# baseboard_rev_0_2.net
KiCad netlist of a schematic drawn in EAGLE
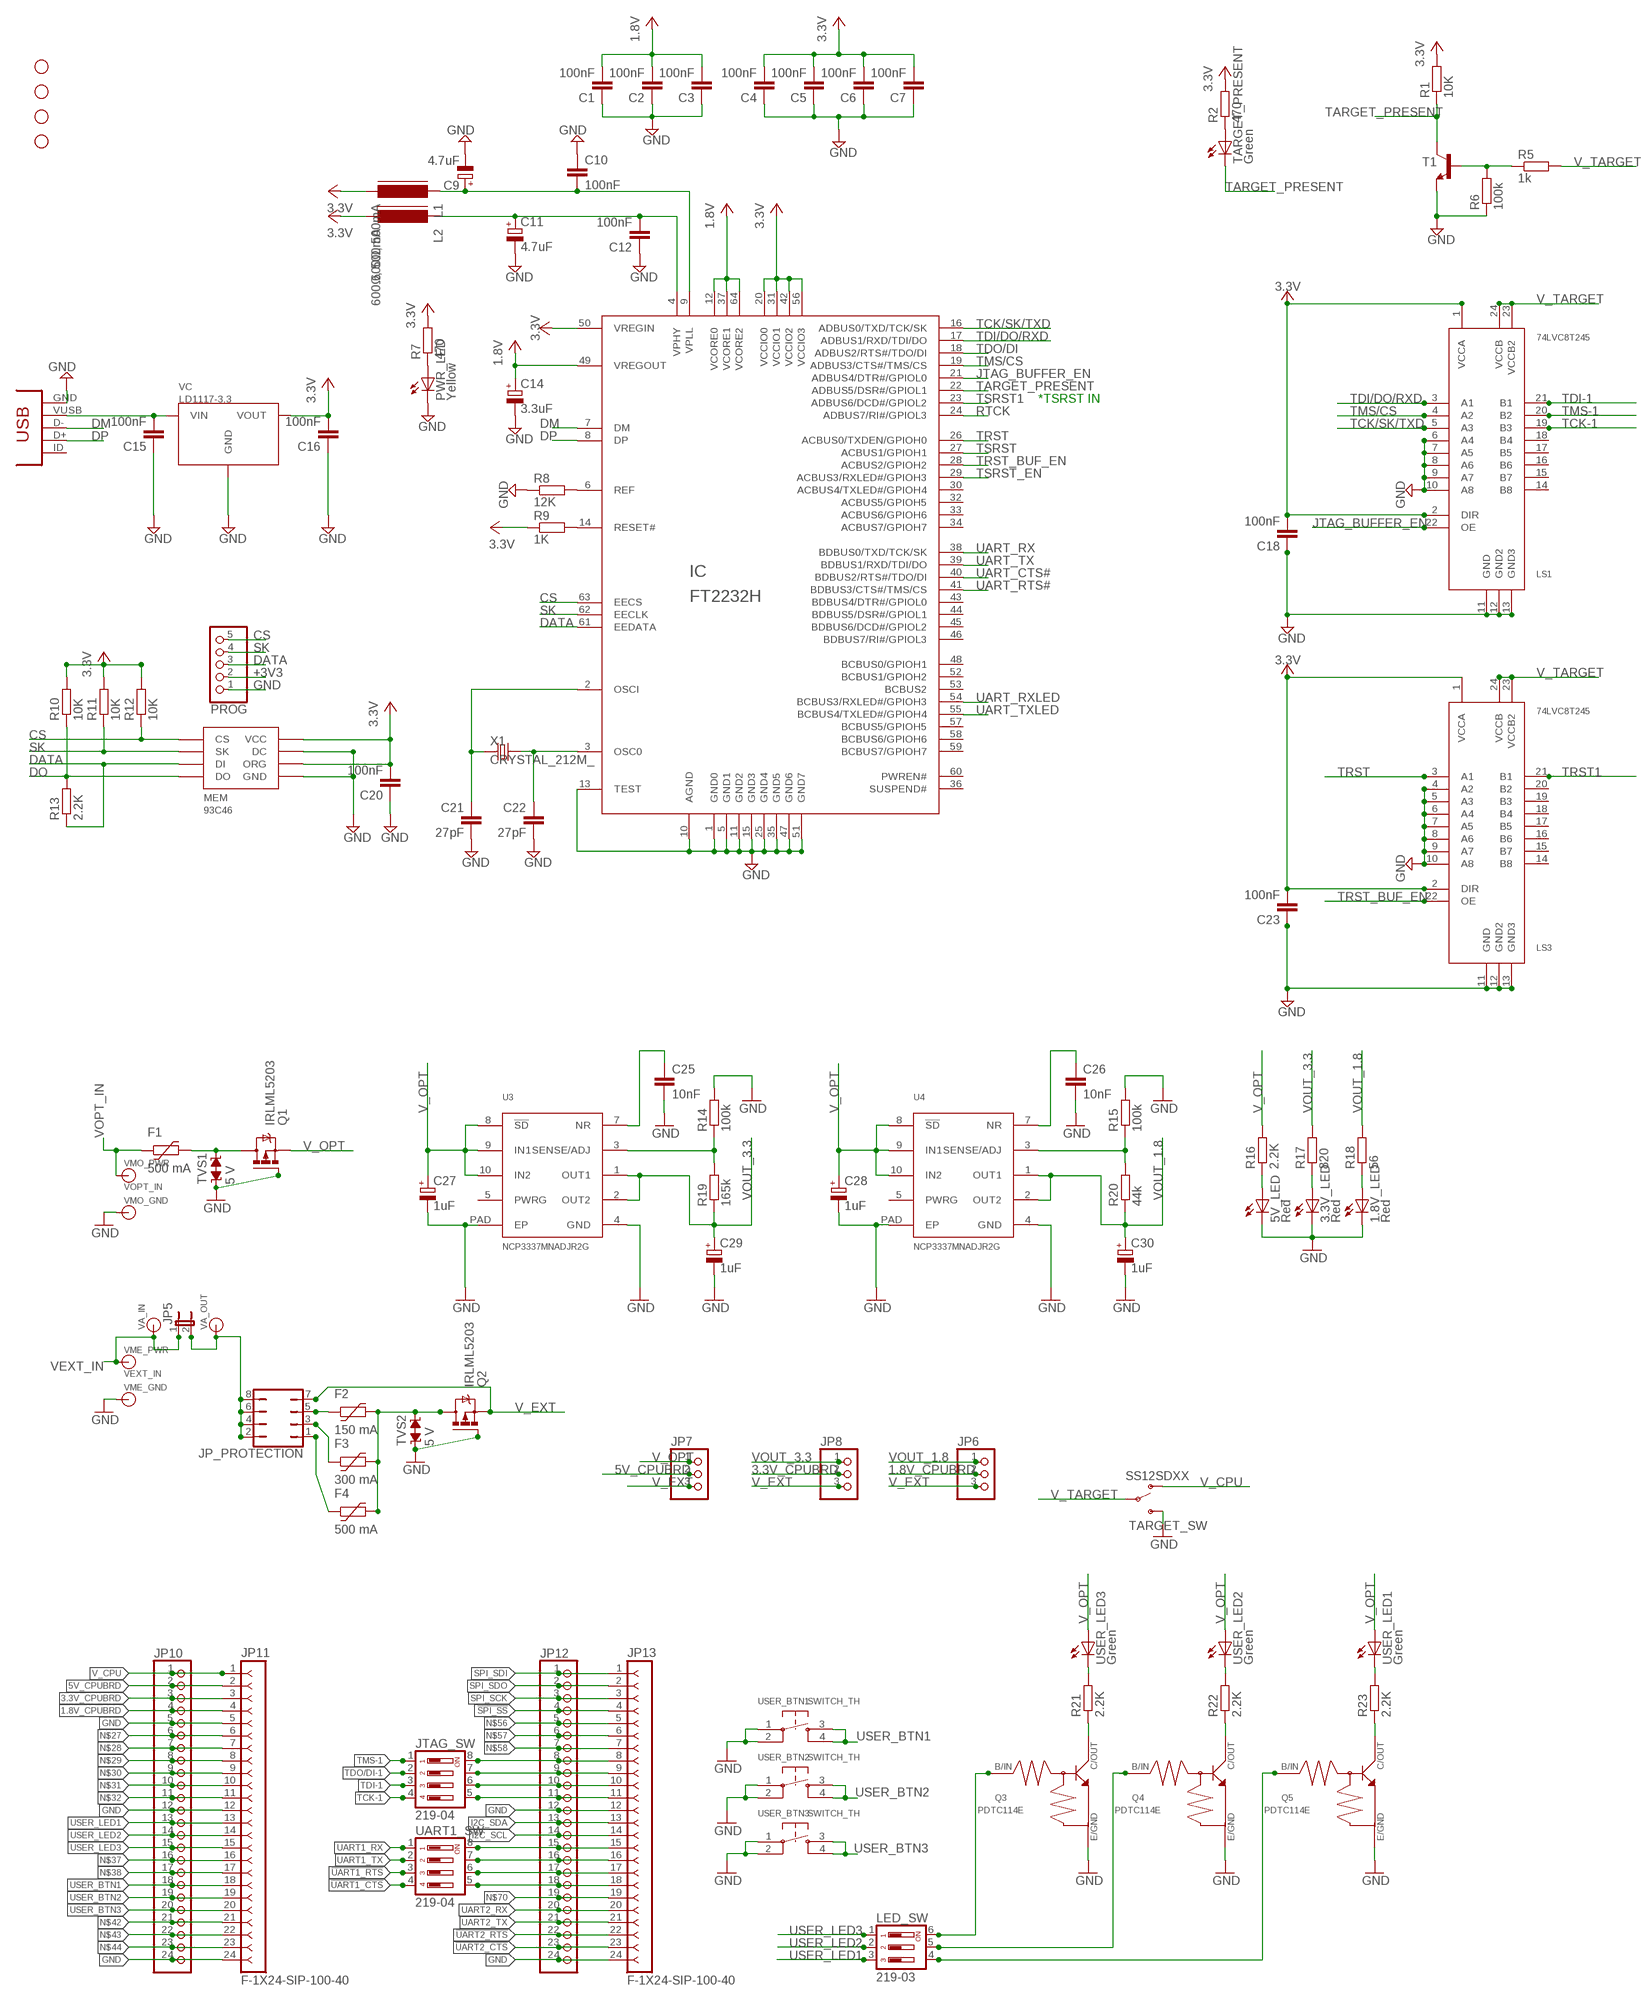
[diagram p0: schematic, sheet 1, part 1 of 2]
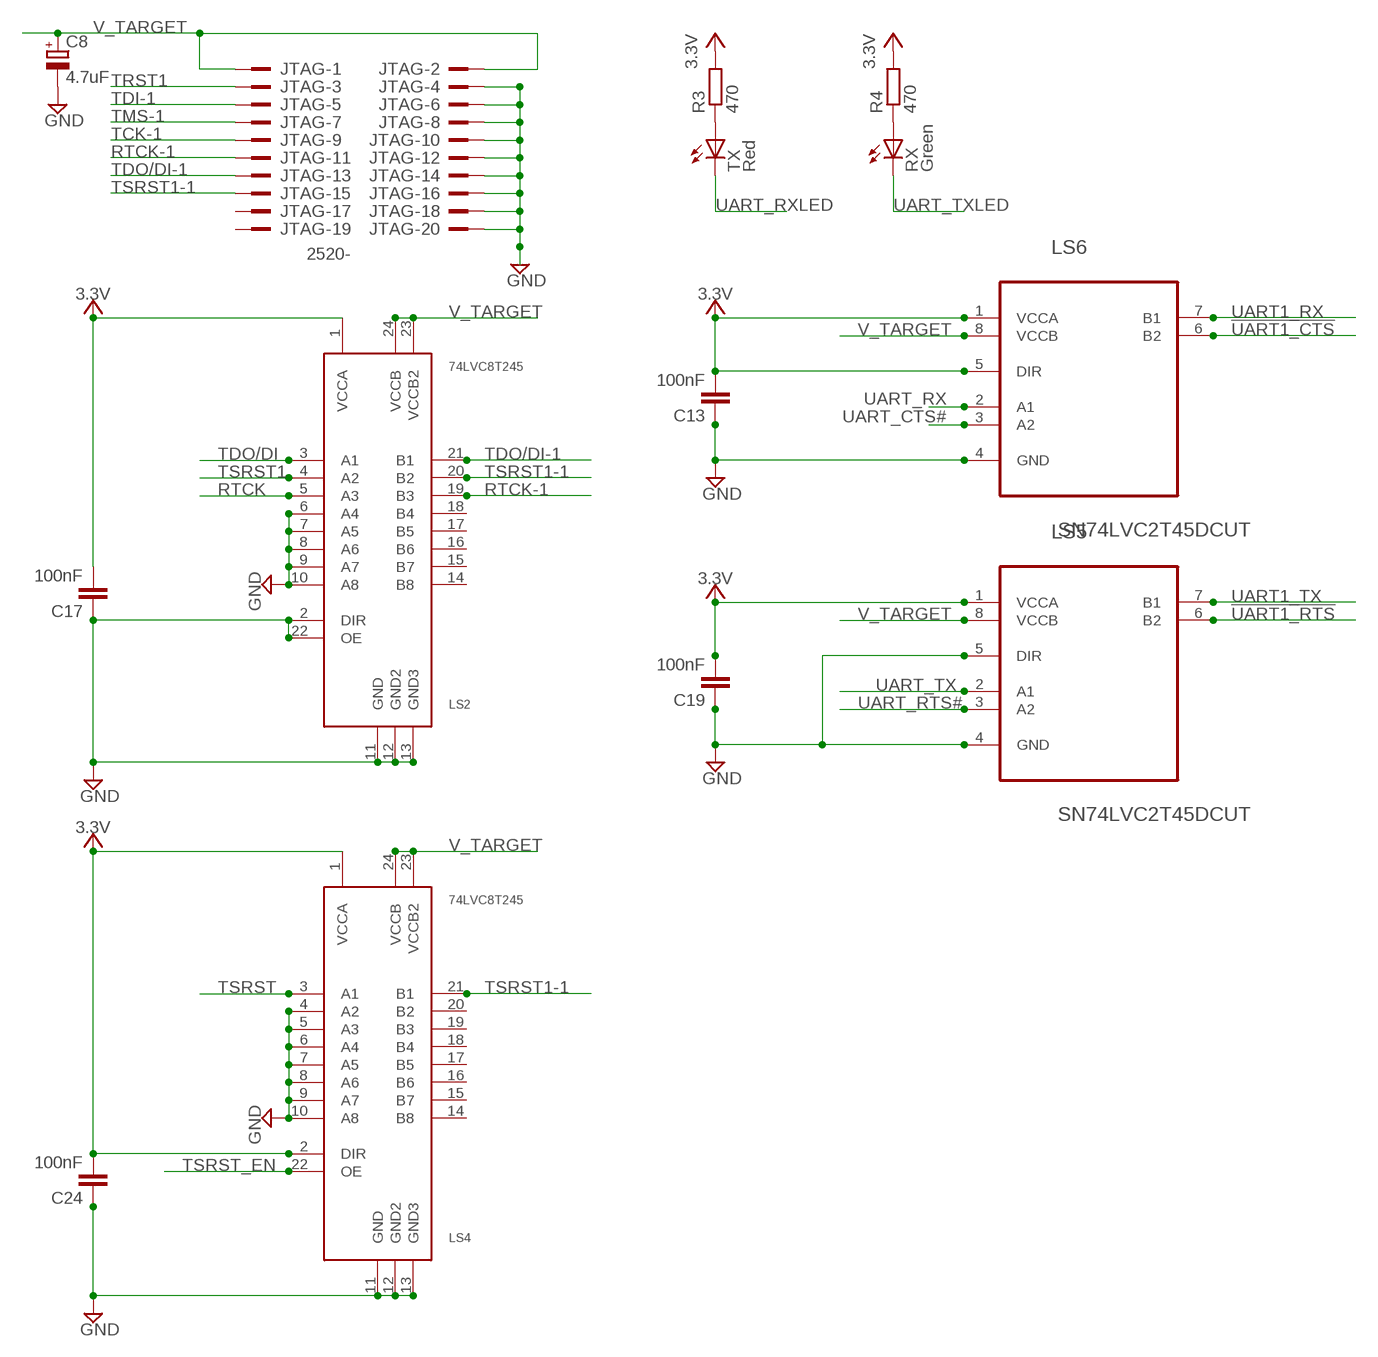
[diagram p1: schematic, sheet 1, part 2 of 2]

(export (version "E")
  (design (tool "Eeschema 10.0.6"))
  (components
    (comp (ref "1.8V_LED")
      (value "Red")
      (footprint "eagle-import:CHIPLED_0805")
      (libsource (lib "eagle-import") (part "LEDCHIPLED_0805"))
    )
    (comp (ref "3.3V_LED")
      (value "Red")
      (footprint "eagle-import:CHIPLED_0805")
      (libsource (lib "eagle-import") (part "LEDCHIPLED_0805"))
    )
    (comp (ref "5V_LED")
      (value "Red")
      (footprint "eagle-import:CHIPLED_0805")
      (libsource (lib "eagle-import") (part "LEDCHIPLED_0805"))
    )
    (comp (ref "C1")
      (value "100nF")
      (footprint "eagle-import:C805")
      (libsource (lib "eagle-import") (part "CAPC805"))
    )
    (comp (ref "C2")
      (value "100nF")
      (footprint "eagle-import:C805")
      (libsource (lib "eagle-import") (part "CAPC805"))
    )
    (comp (ref "C3")
      (value "100nF")
      (footprint "eagle-import:C805")
      (libsource (lib "eagle-import") (part "CAPC805"))
    )
    (comp (ref "C4")
      (value "100nF")
      (footprint "eagle-import:C805")
      (libsource (lib "eagle-import") (part "CAPC805"))
    )
    (comp (ref "C5")
      (value "100nF")
      (footprint "eagle-import:C805")
      (libsource (lib "eagle-import") (part "CAPC805"))
    )
    (comp (ref "C6")
      (value "100nF")
      (footprint "eagle-import:C805")
      (libsource (lib "eagle-import") (part "CAPC805"))
    )
    (comp (ref "C7")
      (value "100nF")
      (footprint "eagle-import:C805")
      (libsource (lib "eagle-import") (part "CAPC805"))
    )
    (comp (ref "C8")
      (value "4.7uF")
      (footprint "eagle-import:SMC_A")
      (libsource (lib "eagle-import") (part "CAP_POLSMC_A"))
    )
    (comp (ref "C9")
      (value "4.7uF")
      (footprint "eagle-import:SMC_A")
      (libsource (lib "eagle-import") (part "CAP_POLSMC_A"))
    )
    (comp (ref "C10")
      (value "100nF")
      (footprint "eagle-import:C805")
      (libsource (lib "eagle-import") (part "CAPC805"))
    )
    (comp (ref "C11")
      (value "4.7uF")
      (footprint "eagle-import:SMC_A")
      (libsource (lib "eagle-import") (part "CAP_POLSMC_A"))
    )
    (comp (ref "C12")
      (value "100nF")
      (footprint "eagle-import:C805")
      (libsource (lib "eagle-import") (part "CAPC805"))
    )
    (comp (ref "C13")
      (value "100nF")
      (footprint "eagle-import:C805")
      (libsource (lib "eagle-import") (part "CAPC805"))
    )
    (comp (ref "C14")
      (value "3.3uF")
      (footprint "eagle-import:SMC_A")
      (libsource (lib "eagle-import") (part "CAP_POLSMC_A"))
    )
    (comp (ref "C15")
      (value "100nF")
      (footprint "eagle-import:C805")
      (libsource (lib "eagle-import") (part "CAPC805"))
    )
    (comp (ref "C16")
      (value "100nF")
      (footprint "eagle-import:C805")
      (libsource (lib "eagle-import") (part "CAPC805"))
    )
    (comp (ref "C17")
      (value "100nF")
      (footprint "eagle-import:C805")
      (libsource (lib "eagle-import") (part "CAPC805"))
    )
    (comp (ref "C18")
      (value "100nF")
      (footprint "eagle-import:C805")
      (libsource (lib "eagle-import") (part "CAPC805"))
    )
    (comp (ref "C19")
      (value "100nF")
      (footprint "eagle-import:C805")
      (libsource (lib "eagle-import") (part "CAPC805"))
    )
    (comp (ref "C20")
      (value "100nF")
      (footprint "eagle-import:C805")
      (libsource (lib "eagle-import") (part "CAPC805"))
    )
    (comp (ref "C21")
      (value "27pF")
      (footprint "eagle-import:C805")
      (libsource (lib "eagle-import") (part "CAPC805"))
    )
    (comp (ref "C22")
      (value "27pF")
      (footprint "eagle-import:C805")
      (libsource (lib "eagle-import") (part "CAPC805"))
    )
    (comp (ref "C23")
      (value "100nF")
      (footprint "eagle-import:C805")
      (libsource (lib "eagle-import") (part "CAPC805"))
    )
    (comp (ref "C24")
      (value "100nF")
      (footprint "eagle-import:C805")
      (libsource (lib "eagle-import") (part "CAPC805"))
    )
    (comp (ref "C25")
      (value "10nF")
      (footprint "eagle-import:C0805")
      (libsource (lib "eagle-import") (part "C-EUC0805"))
    )
    (comp (ref "C26")
      (value "10nF")
      (footprint "eagle-import:C0805")
      (libsource (lib "eagle-import") (part "C-EUC0805"))
    )
    (comp (ref "C27")
      (value "1uF")
      (footprint "eagle-import:PANASONIC_B")
      (libsource (lib "eagle-import") (part "CPOL-EUB"))
    )
    (comp (ref "C28")
      (value "1uF")
      (footprint "eagle-import:PANASONIC_B")
      (libsource (lib "eagle-import") (part "CPOL-EUB"))
    )
    (comp (ref "C29")
      (value "1uF")
      (footprint "eagle-import:PANASONIC_B")
      (libsource (lib "eagle-import") (part "CPOL-EUB"))
    )
    (comp (ref "C30")
      (value "1uF")
      (footprint "eagle-import:PANASONIC_B")
      (libsource (lib "eagle-import") (part "CPOL-EUB"))
    )
    (comp (ref "CONN1")
      (value "CONN_USB")
      (footprint "eagle-import:CONN_USB_MINI-B")
      (libsource (lib "eagle-import") (part "CONN_USB"))
    )
    (comp (ref "F1")
      (value "500 mA")
      (footprint "eagle-import:1206L")
      (libsource (lib "eagle-import") (part "1206L"))
    )
    (comp (ref "F2")
      (value "150 mA")
      (footprint "eagle-import:1206L")
      (libsource (lib "eagle-import") (part "1206L"))
    )
    (comp (ref "F3")
      (value "300 mA")
      (footprint "eagle-import:1206L")
      (libsource (lib "eagle-import") (part "1206L"))
    )
    (comp (ref "F4")
      (value "500 mA")
      (footprint "eagle-import:1206L")
      (libsource (lib "eagle-import") (part "1206L"))
    )
    (comp (ref "IC")
      (value "FT2232H")
      (footprint "eagle-import:LQFP64")
      (libsource (lib "eagle-import") (part "FT2232H"))
    )
    (comp (ref "JP1")
      (value "STAND-OFF")
      (footprint "eagle-import:STAND-OFF")
      (libsource (lib "eagle-import") (part "STAND-OFF"))
    )
    (comp (ref "JP2")
      (value "STAND-OFF")
      (footprint "eagle-import:STAND-OFF")
      (libsource (lib "eagle-import") (part "STAND-OFF"))
    )
    (comp (ref "JP3")
      (value "STAND-OFF")
      (footprint "eagle-import:STAND-OFF")
      (libsource (lib "eagle-import") (part "STAND-OFF"))
    )
    (comp (ref "JP4")
      (value "STAND-OFF")
      (footprint "eagle-import:STAND-OFF")
      (libsource (lib "eagle-import") (part "STAND-OFF"))
    )
    (comp (ref "JP5")
      (value "JUMPER-2PTH")
      (footprint "eagle-import:1X02")
      (libsource (lib "eagle-import") (part "JUMPER-2PTH"))
    )
    (comp (ref "JP6")
      (value "PINHD-1X3")
      (footprint "eagle-import:1X03")
      (libsource (lib "eagle-import") (part "PINHD-1X3"))
    )
    (comp (ref "JP7")
      (value "PINHD-1X3")
      (footprint "eagle-import:1X03")
      (libsource (lib "eagle-import") (part "PINHD-1X3"))
    )
    (comp (ref "JP8")
      (value "PINHD-1X3")
      (footprint "eagle-import:1X03")
      (libsource (lib "eagle-import") (part "PINHD-1X3"))
    )
    (comp (ref "JP10")
      (value "PINHD-1X24")
      (footprint "eagle-import:1X24")
      (libsource (lib "eagle-import") (part "PINHD-1X24"))
    )
    (comp (ref "JP11")
      (value "F-1X24-SIP-100-40")
      (footprint "eagle-import:SIP-100-24-40")
      (libsource (lib "eagle-import") (part "F-1X24-SIP-100-40"))
    )
    (comp (ref "JP12")
      (value "PINHD-1X24")
      (footprint "eagle-import:1X24")
      (libsource (lib "eagle-import") (part "PINHD-1X24"))
    )
    (comp (ref "JP13")
      (value "F-1X24-SIP-100-40")
      (footprint "eagle-import:SIP-100-24-40")
      (libsource (lib "eagle-import") (part "F-1X24-SIP-100-40"))
    )
    (comp (ref "JP_PROTECTION")
      (value "JP4Q")
      (footprint "eagle-import:JP4Q")
      (libsource (lib "eagle-import") (part "JP4Q"))
    )
    (comp (ref "JTAG")
      (value "2520-")
      (footprint "eagle-import:PAK100_2500-20")
      (libsource (lib "eagle-import") (part "2520-"))
    )
    (comp (ref "JTAG_SW")
      (value "219-04")
      (footprint "eagle-import:CTS-219-04")
      (libsource (lib "eagle-import") (part "219-04"))
    )
    (comp (ref "L1")
      (value "600Ω, 500mA")
      (footprint "eagle-import:FB805")
      (libsource (lib "eagle-import") (part "FERRITE_BEAD805"))
    )
    (comp (ref "L2")
      (value "600Ω, 500mA")
      (footprint "eagle-import:FB805")
      (libsource (lib "eagle-import") (part "FERRITE_BEAD805"))
    )
    (comp (ref "LED_SW")
      (value "219-03")
      (footprint "eagle-import:CTS-219-03")
      (libsource (lib "eagle-import") (part "219-03"))
    )
    (comp (ref "LS1")
      (value "74LVC8T245")
      (footprint "eagle-import:TSSOP24")
      (libsource (lib "eagle-import") (part "74LVC8T245"))
    )
    (comp (ref "LS2")
      (value "74LVC8T245")
      (footprint "eagle-import:TSSOP24")
      (libsource (lib "eagle-import") (part "74LVC8T245"))
    )
    (comp (ref "LS3")
      (value "74LVC8T245")
      (footprint "eagle-import:TSSOP24")
      (libsource (lib "eagle-import") (part "74LVC8T245"))
    )
    (comp (ref "LS4")
      (value "74LVC8T245")
      (footprint "eagle-import:TSSOP24")
      (libsource (lib "eagle-import") (part "74LVC8T245"))
    )
    (comp (ref "LS5")
      (value "SN74LVC2T45DCUT")
      (footprint "eagle-import:SOP50P310X90-8N")
      (libsource (lib "eagle-import") (part "SN74LVC2T45DCUT"))
    )
    (comp (ref "LS6")
      (value "SN74LVC2T45DCUT")
      (footprint "eagle-import:SOP50P310X90-8N")
      (libsource (lib "eagle-import") (part "SN74LVC2T45DCUT"))
    )
    (comp (ref "MEM")
      (value "93C46")
      (footprint "eagle-import:SOIC8")
      (libsource (lib "eagle-import") (part "93C46"))
    )
    (comp (ref "PROG")
      (value "PINHD-1X5")
      (footprint "eagle-import:1X05")
      (libsource (lib "eagle-import") (part "PINHD-1X5"))
    )
    (comp (ref "PWR_LED")
      (value "Yellow")
      (footprint "eagle-import:CHIPLED_0805")
      (libsource (lib "eagle-import") (part "led_LEDCHIPLED_0805"))
    )
    (comp (ref "Q1")
      (value "IRLML5203")
      (footprint "eagle-import:MICRO3")
      (libsource (lib "eagle-import") (part "IRLML5203"))
    )
    (comp (ref "Q2")
      (value "IRLML5203")
      (footprint "eagle-import:MICRO3")
      (libsource (lib "eagle-import") (part "IRLML5203"))
    )
    (comp (ref "Q3")
      (value "PDTC114E")
      (footprint "eagle-import:SOT416")
      (libsource (lib "eagle-import") (part "PDTC114E"))
    )
    (comp (ref "Q4")
      (value "PDTC114E")
      (footprint "eagle-import:SOT416")
      (libsource (lib "eagle-import") (part "PDTC114E"))
    )
    (comp (ref "Q5")
      (value "PDTC114E")
      (footprint "eagle-import:SOT416")
      (libsource (lib "eagle-import") (part "PDTC114E"))
    )
    (comp (ref "R1")
      (value "10K")
      (footprint "eagle-import:R805")
      (libsource (lib "eagle-import") (part "RESISTORR805R805"))
    )
    (comp (ref "R2")
      (value "470")
      (footprint "eagle-import:R805")
      (libsource (lib "eagle-import") (part "RESISTORR805R805"))
    )
    (comp (ref "R3")
      (value "470")
      (footprint "eagle-import:R805")
      (libsource (lib "eagle-import") (part "RESISTORR805R805"))
    )
    (comp (ref "R4")
      (value "470")
      (footprint "eagle-import:R805")
      (libsource (lib "eagle-import") (part "RESISTORR805R805"))
    )
    (comp (ref "R5")
      (value "1k")
      (footprint "eagle-import:R805")
      (libsource (lib "eagle-import") (part "RESISTORR805R805"))
    )
    (comp (ref "R6")
      (value "100k")
      (footprint "eagle-import:R805")
      (libsource (lib "eagle-import") (part "RESISTORR805R805"))
    )
    (comp (ref "R7")
      (value "470")
      (footprint "eagle-import:R805")
      (libsource (lib "eagle-import") (part "RESISTORR805R805"))
    )
    (comp (ref "R8")
      (value "12K")
      (footprint "eagle-import:R805")
      (libsource (lib "eagle-import") (part "RESISTORR805R805"))
    )
    (comp (ref "R9")
      (value "1K")
      (footprint "eagle-import:R805")
      (libsource (lib "eagle-import") (part "RESISTORR805R805"))
    )
    (comp (ref "R10")
      (value "10K")
      (footprint "eagle-import:R805")
      (libsource (lib "eagle-import") (part "RESISTORR805R805"))
    )
    (comp (ref "R11")
      (value "10K")
      (footprint "eagle-import:R805")
      (libsource (lib "eagle-import") (part "RESISTORR805R805"))
    )
    (comp (ref "R12")
      (value "10K")
      (footprint "eagle-import:R805")
      (libsource (lib "eagle-import") (part "RESISTORR805R805"))
    )
    (comp (ref "R13")
      (value "2.2K")
      (footprint "eagle-import:R805")
      (libsource (lib "eagle-import") (part "RESISTORR805R805"))
    )
    (comp (ref "R14")
      (value "100k")
      (footprint "eagle-import:R0805")
      (libsource (lib "eagle-import") (part "R-EU_R0805"))
    )
    (comp (ref "R15")
      (value "100k")
      (footprint "eagle-import:R0805")
      (libsource (lib "eagle-import") (part "R-EU_R0805"))
    )
    (comp (ref "R16")
      (value "2.2K")
      (footprint "eagle-import:R0805")
      (libsource (lib "eagle-import") (part "R-EU_R0805"))
    )
    (comp (ref "R17")
      (value "820")
      (footprint "eagle-import:R0805")
      (libsource (lib "eagle-import") (part "R-EU_R0805"))
    )
    (comp (ref "R18")
      (value "56")
      (footprint "eagle-import:R0805")
      (libsource (lib "eagle-import") (part "R-EU_R0805"))
    )
    (comp (ref "R19")
      (value "165k")
      (footprint "eagle-import:R0805")
      (libsource (lib "eagle-import") (part "R-EU_R0805"))
    )
    (comp (ref "R20")
      (value "44k")
      (footprint "eagle-import:R0805")
      (libsource (lib "eagle-import") (part "R-EU_R0805"))
    )
    (comp (ref "R21")
      (value "2.2K")
      (footprint "eagle-import:R0805")
      (libsource (lib "eagle-import") (part "R-EU_R0805"))
    )
    (comp (ref "R22")
      (value "2.2K")
      (footprint "eagle-import:R0805")
      (libsource (lib "eagle-import") (part "R-EU_R0805"))
    )
    (comp (ref "R23")
      (value "2.2K")
      (footprint "eagle-import:R0805")
      (libsource (lib "eagle-import") (part "R-EU_R0805"))
    )
    (comp (ref "RX")
      (value "Green")
      (footprint "eagle-import:CHIPLED_0805")
      (libsource (lib "eagle-import") (part "led_LEDCHIPLED_0805"))
    )
    (comp (ref "T1")
      (value "NPNSOT23BEC")
      (footprint "eagle-import:SOT23-BEC")
      (libsource (lib "eagle-import") (part "NPNSOT23BEC"))
    )
    (comp (ref "TARGET_PRESENT")
      (value "Green")
      (footprint "eagle-import:CHIPLED_0805")
      (libsource (lib "eagle-import") (part "led_LEDCHIPLED_0805"))
    )
    (comp (ref "TARGET_SW")
      (value "SS12SDXX")
      (footprint "eagle-import:SS12SDXX")
      (libsource (lib "eagle-import") (part "SS12SDXX"))
    )
    (comp (ref "TVS1")
      (value "5 V")
      (footprint "eagle-import:TVS0805")
      (libsource (lib "eagle-import") (part "TVS-0805"))
    )
    (comp (ref "TVS2")
      (value "5 V")
      (footprint "eagle-import:TVS0805")
      (libsource (lib "eagle-import") (part "TVS-0805"))
    )
    (comp (ref "TX")
      (value "Red")
      (footprint "eagle-import:CHIPLED_0805")
      (libsource (lib "eagle-import") (part "led_LEDCHIPLED_0805"))
    )
    (comp (ref "U3")
      (value "NCP3337MNADJR2G")
      (footprint "eagle-import:DFN10")
      (libsource (lib "eagle-import") (part "NCP3337"))
    )
    (comp (ref "U4")
      (value "NCP3337MNADJR2G")
      (footprint "eagle-import:DFN10")
      (libsource (lib "eagle-import") (part "NCP3337"))
    )
    (comp (ref "UART1_SW")
      (value "219-04")
      (footprint "eagle-import:CTS-219-04")
      (libsource (lib "eagle-import") (part "219-04"))
    )
    (comp (ref "USER_BTN1")
      (value "SWITCH_TH")
      (footprint "eagle-import:SWITCH_TROUGHHOLE")
      (libsource (lib "eagle-import") (part "SWITCH_TH"))
    )
    (comp (ref "USER_BTN2")
      (value "SWITCH_TH")
      (footprint "eagle-import:SWITCH_TROUGHHOLE")
      (libsource (lib "eagle-import") (part "SWITCH_TH"))
    )
    (comp (ref "USER_BTN3")
      (value "SWITCH_TH")
      (footprint "eagle-import:SWITCH_TROUGHHOLE")
      (libsource (lib "eagle-import") (part "SWITCH_TH"))
    )
    (comp (ref "USER_LED1")
      (value "Green")
      (footprint "eagle-import:CHIPLED_0805")
      (libsource (lib "eagle-import") (part "LEDCHIPLED_0805"))
    )
    (comp (ref "USER_LED2")
      (value "Green")
      (footprint "eagle-import:CHIPLED_0805")
      (libsource (lib "eagle-import") (part "LEDCHIPLED_0805"))
    )
    (comp (ref "USER_LED3")
      (value "Green")
      (footprint "eagle-import:CHIPLED_0805")
      (libsource (lib "eagle-import") (part "LEDCHIPLED_0805"))
    )
    (comp (ref "VA_IN")
      (value "BANANA_CONN")
      (footprint "eagle-import:BANANA_CONN")
      (libsource (lib "eagle-import") (part "BANANA_CONN"))
    )
    (comp (ref "VA_OUT")
      (value "BANANA_CONN")
      (footprint "eagle-import:BANANA_CONN")
      (libsource (lib "eagle-import") (part "BANANA_CONN"))
    )
    (comp (ref "VC")
      (value "LD1117-3.3")
      (footprint "eagle-import:SOT223")
      (libsource (lib "eagle-import") (part "LD1117-3.3"))
    )
    (comp (ref "VME_GND")
      (value "BANANA_CONN")
      (footprint "eagle-import:BANANA_CONN")
      (libsource (lib "eagle-import") (part "BANANA_CONN"))
    )
    (comp (ref "VME_PWR")
      (value "VEXT_IN")
      (footprint "eagle-import:BANANA_CONN")
      (libsource (lib "eagle-import") (part "BANANA_CONN"))
    )
    (comp (ref "VMO_GND")
      (value "BANANA_CONN")
      (footprint "eagle-import:BANANA_CONN")
      (libsource (lib "eagle-import") (part "BANANA_CONN"))
    )
    (comp (ref "VMO_PWR")
      (value "VOPT_IN")
      (footprint "eagle-import:BANANA_CONN")
      (libsource (lib "eagle-import") (part "BANANA_CONN"))
    )
    (comp (ref "X1")
      (value "CRYSTAL_212M_")
      (footprint "eagle-import:4X6")
      (libsource (lib "eagle-import") (part "CRYSTAL_212M_"))
    )
  )
  (nets
    (net (code "1") (name "/CS") (class "Default")
      (node (ref "IC") (pin "63") (pinfunction "EECS_63") (pintype "bidirectional"))
      (node (ref "MEM") (pin "1") (pinfunction "CS_1") (pintype "bidirectional"))
      (node (ref "PROG") (pin "5") (pinfunction "5_5") (pintype "passive"))
      (node (ref "R12") (pin "1") (pinfunction "1_1") (pintype "passive"))
    )
    (net (code "2") (name "/DATA") (class "Default")
      (node (ref "IC") (pin "61") (pinfunction "EEDATA_61") (pintype "bidirectional"))
      (node (ref "MEM") (pin "3") (pinfunction "DI_3") (pintype "bidirectional"))
      (node (ref "PROG") (pin "3") (pinfunction "3_3") (pintype "passive"))
      (node (ref "R13") (pin "1") (pinfunction "1_1") (pintype "passive"))
    )
    (net (code "3") (name "/DM") (class "Default")
      (node (ref "CONN1") (pin "D-") (pinfunction "D-_D-") (pintype "bidirectional"))
      (node (ref "IC") (pin "7") (pinfunction "DM_7") (pintype "bidirectional"))
    )
    (net (code "4") (name "/DO") (class "Default")
      (node (ref "MEM") (pin "4") (pinfunction "DO_4") (pintype "bidirectional"))
      (node (ref "R10") (pin "1") (pinfunction "1_1") (pintype "passive"))
      (node (ref "R13") (pin "2") (pinfunction "2_2") (pintype "passive"))
    )
    (net (code "5") (name "/DP") (class "Default")
      (node (ref "CONN1") (pin "D+") (pinfunction "D+_D+") (pintype "bidirectional"))
      (node (ref "IC") (pin "8") (pinfunction "DP_8") (pintype "bidirectional"))
    )
    (net (code "6") (name "/JTAG_BUFFER_EN") (class "Default")
      (node (ref "IC") (pin "21") (pinfunction "ADBUS4/DTR#/GPIOL0_21") (pintype "bidirectional"))
      (node (ref "LS1") (pin "22") (pinfunction "OE_22") (pintype "bidirectional"))
    )
    (net (code "7") (name "/RTCK") (class "Default")
      (node (ref "IC") (pin "24") (pinfunction "ADBUS7/RI#/GPIOL3_24") (pintype "bidirectional"))
      (node (ref "LS2") (pin "5") (pinfunction "A3_5") (pintype "bidirectional"))
    )
    (net (code "8") (name "/RTCK-1") (class "Default")
      (node (ref "JTAG") (pin "11") (pinfunction "KL_11") (pintype "passive"))
      (node (ref "LS2") (pin "19") (pinfunction "B3_19") (pintype "bidirectional"))
    )
    (net (code "9") (name "/SK") (class "Default")
      (node (ref "IC") (pin "62") (pinfunction "EECLK_62") (pintype "bidirectional"))
      (node (ref "MEM") (pin "2") (pinfunction "SK_2") (pintype "bidirectional"))
      (node (ref "PROG") (pin "4") (pinfunction "4_4") (pintype "passive"))
      (node (ref "R11") (pin "1") (pinfunction "1_1") (pintype "passive"))
    )
    (net (code "10") (name "/TARGET_PRESENT") (class "Default")
      (node (ref "IC") (pin "22") (pinfunction "ADBUS5/DSR#/GPIOL1_22") (pintype "bidirectional"))
      (node (ref "R1") (pin "1") (pinfunction "1_1") (pintype "passive"))
      (node (ref "T1") (pin "C") (pinfunction "C_C") (pintype "passive"))
      (node (ref "TARGET_PRESENT") (pin "C") (pinfunction "C_C") (pintype "passive"))
    )
    (net (code "11") (name "/TCK{slash}SK{slash}TXD") (class "Default")
      (node (ref "IC") (pin "16") (pinfunction "ADBUS0/TXD/TCK/SK_16") (pintype "bidirectional"))
      (node (ref "LS1") (pin "5") (pinfunction "A3_5") (pintype "bidirectional"))
    )
    (net (code "12") (name "/TDI{slash}DO{slash}RXD") (class "Default")
      (node (ref "IC") (pin "17") (pinfunction "ADBUS1/RXD/TDI/DO_17") (pintype "bidirectional"))
      (node (ref "LS1") (pin "3") (pinfunction "A1_3") (pintype "bidirectional"))
    )
    (net (code "13") (name "/TDO{slash}DI") (class "Default")
      (node (ref "IC") (pin "18") (pinfunction "ADBUS2/RTS#/TDO/DI_18") (pintype "bidirectional"))
      (node (ref "LS2") (pin "3") (pinfunction "A1_3") (pintype "bidirectional"))
    )
    (net (code "14") (name "/TMS{slash}CS") (class "Default")
      (node (ref "IC") (pin "19") (pinfunction "ADBUS3/CTS#/TMS/CS_19") (pintype "bidirectional"))
      (node (ref "LS1") (pin "4") (pinfunction "A2_4") (pintype "bidirectional"))
    )
    (net (code "15") (name "/TRST") (class "Default")
      (node (ref "IC") (pin "26") (pinfunction "ACBUS0/TXDEN/GPIOH0_26") (pintype "bidirectional"))
      (node (ref "LS3") (pin "3") (pinfunction "A1_3") (pintype "bidirectional"))
    )
    (net (code "16") (name "/TRST1") (class "Default")
      (node (ref "JTAG") (pin "3") (pinfunction "KL_3") (pintype "passive"))
      (node (ref "LS3") (pin "21") (pinfunction "B1_21") (pintype "bidirectional"))
    )
    (net (code "17") (name "/TRST_BUF_EN") (class "Default")
      (node (ref "IC") (pin "28") (pinfunction "ACBUS2/GPIOH2_28") (pintype "bidirectional"))
      (node (ref "LS3") (pin "22") (pinfunction "OE_22") (pintype "bidirectional"))
    )
    (net (code "18") (name "/TSRST") (class "Default")
      (node (ref "IC") (pin "27") (pinfunction "ACBUS1/GPIOH1_27") (pintype "bidirectional"))
      (node (ref "LS4") (pin "3") (pinfunction "A1_3") (pintype "bidirectional"))
    )
    (net (code "19") (name "/TSRST1") (class "Default")
      (node (ref "IC") (pin "23") (pinfunction "ADBUS6/DCD#/GPIOL2_23") (pintype "bidirectional"))
      (node (ref "LS2") (pin "4") (pinfunction "A2_4") (pintype "bidirectional"))
    )
    (net (code "20") (name "/TSRST1-1") (class "Default")
      (node (ref "JTAG") (pin "15") (pinfunction "KL_15") (pintype "passive"))
      (node (ref "LS2") (pin "20") (pinfunction "B2_20") (pintype "bidirectional"))
      (node (ref "LS4") (pin "21") (pinfunction "B1_21") (pintype "bidirectional"))
    )
    (net (code "21") (name "/TSRST_EN") (class "Default")
      (node (ref "IC") (pin "29") (pinfunction "ACBUS3/RXLED#/GPIOH3_29") (pintype "bidirectional"))
      (node (ref "LS4") (pin "22") (pinfunction "OE_22") (pintype "bidirectional"))
    )
    (net (code "22") (name "/UART_CTS#") (class "Default")
      (node (ref "IC") (pin "40") (pinfunction "BDBUS2/RTS#/TDO/DI_40") (pintype "bidirectional"))
      (node (ref "LS6") (pin "3") (pinfunction "A2_3") (pintype "bidirectional"))
    )
    (net (code "23") (name "/UART_RTS#") (class "Default")
      (node (ref "IC") (pin "41") (pinfunction "BDBUS3/CTS#/TMS/CS_41") (pintype "bidirectional"))
      (node (ref "LS5") (pin "3") (pinfunction "A2_3") (pintype "bidirectional"))
    )
    (net (code "24") (name "/UART_RX") (class "Default")
      (node (ref "IC") (pin "38") (pinfunction "BDBUS0/TXD/TCK/SK_38") (pintype "bidirectional"))
      (node (ref "LS6") (pin "2") (pinfunction "A1_2") (pintype "bidirectional"))
    )
    (net (code "25") (name "/UART_RXLED") (class "Default")
      (node (ref "IC") (pin "54") (pinfunction "BCBUS3/RXLED#/GPIOH3_54") (pintype "bidirectional"))
      (node (ref "TX") (pin "C") (pinfunction "C_C") (pintype "passive"))
    )
    (net (code "26") (name "/UART_TX") (class "Default")
      (node (ref "IC") (pin "39") (pinfunction "BDBUS1/RXD/TDI/DO_39") (pintype "bidirectional"))
      (node (ref "LS5") (pin "2") (pinfunction "A1_2") (pintype "bidirectional"))
    )
    (net (code "27") (name "/UART_TXLED") (class "Default")
      (node (ref "IC") (pin "55") (pinfunction "BCBUS4/TXLED#/GPIOH4_55") (pintype "bidirectional"))
      (node (ref "RX") (pin "C") (pinfunction "C_C") (pintype "passive"))
    )
    (net (code "28") (name "/VEXT_IN") (class "Default")
      (node (ref "JP5") (pin "1") (pinfunction "1_1") (pintype "passive"))
      (node (ref "JP5") (pin "2") (pinfunction "2_2") (pintype "passive"))
      (node (ref "JP_PROTECTION") (pin "2") (pinfunction "2_2") (pintype "passive"))
      (node (ref "JP_PROTECTION") (pin "4") (pinfunction "4_4") (pintype "passive"))
      (node (ref "JP_PROTECTION") (pin "6") (pinfunction "6_6") (pintype "passive"))
      (node (ref "JP_PROTECTION") (pin "8") (pinfunction "8_8") (pintype "passive"))
      (node (ref "VA_IN") (pin "P$1") (pinfunction "1_P$1") (pintype "passive"))
      (node (ref "VA_OUT") (pin "P$1") (pinfunction "1_P$1") (pintype "passive"))
      (node (ref "VME_PWR") (pin "P$1") (pinfunction "1_P$1") (pintype "passive"))
    )
    (net (code "29") (name "/VOPT_IN") (class "Default")
      (node (ref "F1") (pin "P$1") (pinfunction "1_P$1") (pintype "passive"))
      (node (ref "VMO_PWR") (pin "P$1") (pinfunction "1_P$1") (pintype "passive"))
    )
    (net (code "30") (name "/VOUT_1.8") (class "Default")
      (node (ref "C30") (pin "+") (pinfunction "+_+") (pintype "passive"))
      (node (ref "JP6") (pin "1") (pinfunction "1_1") (pintype "passive"))
      (node (ref "R18") (pin "2") (pinfunction "2_2") (pintype "passive"))
      (node (ref "R20") (pin "1") (pinfunction "1_1") (pintype "passive"))
      (node (ref "U4") (pin "1") (pinfunction "OUT1_1") (pintype "bidirectional"))
      (node (ref "U4") (pin "2") (pinfunction "OUT2_2") (pintype "bidirectional"))
    )
    (net (code "31") (name "/VOUT_3.3") (class "Default")
      (node (ref "C29") (pin "+") (pinfunction "+_+") (pintype "passive"))
      (node (ref "JP8") (pin "1") (pinfunction "1_1") (pintype "passive"))
      (node (ref "R17") (pin "2") (pinfunction "2_2") (pintype "passive"))
      (node (ref "R19") (pin "1") (pinfunction "1_1") (pintype "passive"))
      (node (ref "U3") (pin "1") (pinfunction "OUT1_1") (pintype "bidirectional"))
      (node (ref "U3") (pin "2") (pinfunction "OUT2_2") (pintype "bidirectional"))
    )
    (net (code "32") (name "/V_EXT") (class "Default")
      (node (ref "JP6") (pin "3") (pinfunction "3_3") (pintype "passive"))
      (node (ref "JP7") (pin "3") (pinfunction "3_3") (pintype "passive"))
      (node (ref "JP8") (pin "3") (pinfunction "3_3") (pintype "passive"))
      (node (ref "JP_PROTECTION") (pin "7") (pinfunction "7_7") (pintype "passive"))
      (node (ref "Q2") (pin "2") (pinfunction "S_2") (pintype "passive"))
    )
    (net (code "33") (name "/V_OPT") (class "Default")
      (node (ref "C27") (pin "+") (pinfunction "+_+") (pintype "passive"))
      (node (ref "C28") (pin "+") (pinfunction "+_+") (pintype "passive"))
      (node (ref "JP7") (pin "1") (pinfunction "1_1") (pintype "passive"))
      (node (ref "Q1") (pin "2") (pinfunction "S_2") (pintype "passive"))
      (node (ref "R16") (pin "2") (pinfunction "2_2") (pintype "passive"))
      (node (ref "U3") (pin "10") (pinfunction "IN2_10") (pintype "bidirectional"))
      (node (ref "U3") (pin "8") (pinfunction "~{SD}_8") (pintype "bidirectional"))
      (node (ref "U3") (pin "9") (pinfunction "IN1_9") (pintype "bidirectional"))
      (node (ref "U4") (pin "10") (pinfunction "IN2_10") (pintype "bidirectional"))
      (node (ref "U4") (pin "8") (pinfunction "~{SD}_8") (pintype "bidirectional"))
      (node (ref "U4") (pin "9") (pinfunction "IN1_9") (pintype "bidirectional"))
      (node (ref "USER_LED1") (pin "A") (pinfunction "A_A") (pintype "passive"))
      (node (ref "USER_LED2") (pin "A") (pinfunction "A_A") (pintype "passive"))
      (node (ref "USER_LED3") (pin "A") (pinfunction "A_A") (pintype "passive"))
    )
    (net (code "34") (name "/V_TARGET") (class "Default")
      (node (ref "C8") (pin "+") (pinfunction "+_+") (pintype "passive"))
      (node (ref "JTAG") (pin "1") (pinfunction "KL_1") (pintype "passive"))
      (node (ref "JTAG") (pin "2") (pinfunction "KL_2") (pintype "passive"))
      (node (ref "LS1") (pin "23") (pinfunction "VCCB2_23") (pintype "bidirectional"))
      (node (ref "LS1") (pin "24") (pinfunction "VCCB_24") (pintype "bidirectional"))
      (node (ref "LS2") (pin "23") (pinfunction "VCCB2_23") (pintype "bidirectional"))
      (node (ref "LS2") (pin "24") (pinfunction "VCCB_24") (pintype "bidirectional"))
      (node (ref "LS3") (pin "23") (pinfunction "VCCB2_23") (pintype "bidirectional"))
      (node (ref "LS3") (pin "24") (pinfunction "VCCB_24") (pintype "bidirectional"))
      (node (ref "LS4") (pin "23") (pinfunction "VCCB2_23") (pintype "bidirectional"))
      (node (ref "LS4") (pin "24") (pinfunction "VCCB_24") (pintype "bidirectional"))
      (node (ref "LS5") (pin "8") (pinfunction "VCCB_8") (pintype "power_in"))
      (node (ref "LS6") (pin "8") (pinfunction "VCCB_8") (pintype "power_in"))
      (node (ref "R5") (pin "2") (pinfunction "2_2") (pintype "passive"))
      (node (ref "TARGET_SW") (pin "2") (pinfunction "2_2") (pintype "passive"))
    )
    (net (code "35") (name "/~{SPI_SS}") (class "Default")
      (node (ref "JP12") (pin "4") (pinfunction "4_4") (pintype "passive"))
      (node (ref "JP13") (pin "4") (pinfunction "4_4") (pintype "passive"))
    )
    (net (code "36") (name "/~{UART1_CTS}") (class "Default")
      (node (ref "LS6") (pin "6") (pinfunction "B2_6") (pintype "bidirectional"))
      (node (ref "UART1_SW") (pin "4") (pinfunction "4_4") (pintype "passive"))
    )
    (net (code "37") (name "/~{UART1_RTS}") (class "Default")
      (node (ref "LS5") (pin "6") (pinfunction "B2_6") (pintype "bidirectional"))
      (node (ref "UART1_SW") (pin "3") (pinfunction "3_3") (pintype "passive"))
    )
    (net (code "38") (name "/~{UART2_CTS}") (class "Default")
      (node (ref "JP12") (pin "23") (pinfunction "23_23") (pintype "passive"))
      (node (ref "JP13") (pin "23") (pinfunction "23_23") (pintype "passive"))
    )
    (net (code "39") (name "/~{UART2_RTS}") (class "Default")
      (node (ref "JP12") (pin "22") (pinfunction "22_22") (pintype "passive"))
      (node (ref "JP13") (pin "22") (pinfunction "22_22") (pintype "passive"))
    )
    (net (code "40") (name "1.8V") (class "Default")
      (node (ref "C1") (pin "2") (pinfunction "2_2") (pintype "passive"))
      (node (ref "C14") (pin "+") (pinfunction "+_+") (pintype "passive"))
      (node (ref "C2") (pin "2") (pinfunction "2_2") (pintype "passive"))
      (node (ref "C3") (pin "2") (pinfunction "2_2") (pintype "passive"))
      (node (ref "IC") (pin "12") (pinfunction "VCORE0_12") (pintype "bidirectional"))
      (node (ref "IC") (pin "37") (pinfunction "VCORE1_37") (pintype "bidirectional"))
      (node (ref "IC") (pin "49") (pinfunction "VREGOUT_49") (pintype "bidirectional"))
      (node (ref "IC") (pin "64") (pinfunction "VCORE2_64") (pintype "bidirectional"))
    )
    (net (code "41") (name "1.8V_CPUBRD") (class "Default")
      (node (ref "JP10") (pin "4") (pinfunction "4_4") (pintype "passive"))
      (node (ref "JP11") (pin "4") (pinfunction "4_4") (pintype "passive"))
      (node (ref "JP6") (pin "2") (pinfunction "2_2") (pintype "passive"))
    )
    (net (code "42") (name "3.3V") (class "Default")
      (node (ref "C13") (pin "2") (pinfunction "2_2") (pintype "passive"))
      (node (ref "C16") (pin "2") (pinfunction "2_2") (pintype "passive"))
      (node (ref "C17") (pin "2") (pinfunction "2_2") (pintype "passive"))
      (node (ref "C18") (pin "2") (pinfunction "2_2") (pintype "passive"))
      (node (ref "C19") (pin "2") (pinfunction "2_2") (pintype "passive"))
      (node (ref "C20") (pin "2") (pinfunction "2_2") (pintype "passive"))
      (node (ref "C23") (pin "2") (pinfunction "2_2") (pintype "passive"))
      (node (ref "C24") (pin "2") (pinfunction "2_2") (pintype "passive"))
      (node (ref "C4") (pin "2") (pinfunction "2_2") (pintype "passive"))
      (node (ref "C5") (pin "2") (pinfunction "2_2") (pintype "passive"))
      (node (ref "C6") (pin "2") (pinfunction "2_2") (pintype "passive"))
      (node (ref "C7") (pin "2") (pinfunction "2_2") (pintype "passive"))
      (node (ref "IC") (pin "20") (pinfunction "VCCIO0_20") (pintype "bidirectional"))
      (node (ref "IC") (pin "31") (pinfunction "VCCIO1_31") (pintype "bidirectional"))
      (node (ref "IC") (pin "42") (pinfunction "VCCIO2_42") (pintype "bidirectional"))
      (node (ref "IC") (pin "50") (pinfunction "VREGIN_50") (pintype "bidirectional"))
      (node (ref "IC") (pin "56") (pinfunction "VCCIO3_56") (pintype "bidirectional"))
      (node (ref "L1") (pin "2") (pinfunction "2_2") (pintype "passive"))
      (node (ref "L2") (pin "2") (pinfunction "2_2") (pintype "passive"))
      (node (ref "LS1") (pin "1") (pinfunction "VCCA_1") (pintype "bidirectional"))
      (node (ref "LS1") (pin "2") (pinfunction "DIR_2") (pintype "bidirectional"))
      (node (ref "LS2") (pin "1") (pinfunction "VCCA_1") (pintype "bidirectional"))
      (node (ref "LS3") (pin "1") (pinfunction "VCCA_1") (pintype "bidirectional"))
      (node (ref "LS3") (pin "2") (pinfunction "DIR_2") (pintype "bidirectional"))
      (node (ref "LS4") (pin "1") (pinfunction "VCCA_1") (pintype "bidirectional"))
      (node (ref "LS4") (pin "2") (pinfunction "DIR_2") (pintype "bidirectional"))
      (node (ref "LS5") (pin "1") (pinfunction "VCCA_1") (pintype "power_in"))
      (node (ref "LS6") (pin "1") (pinfunction "VCCA_1") (pintype "power_in"))
      (node (ref "LS6") (pin "5") (pinfunction "DIR_5") (pintype "input"))
      (node (ref "MEM") (pin "6") (pinfunction "ORG_6") (pintype "bidirectional"))
      (node (ref "MEM") (pin "8") (pinfunction "VCC_8") (pintype "bidirectional"))
      (node (ref "PROG") (pin "2") (pinfunction "2_2") (pintype "passive"))
      (node (ref "R1") (pin "2") (pinfunction "2_2") (pintype "passive"))
      (node (ref "R10") (pin "2") (pinfunction "2_2") (pintype "passive"))
      (node (ref "R11") (pin "2") (pinfunction "2_2") (pintype "passive"))
      (node (ref "R12") (pin "2") (pinfunction "2_2") (pintype "passive"))
      (node (ref "R2") (pin "2") (pinfunction "2_2") (pintype "passive"))
      (node (ref "R3") (pin "2") (pinfunction "2_2") (pintype "passive"))
      (node (ref "R4") (pin "2") (pinfunction "2_2") (pintype "passive"))
      (node (ref "R7") (pin "2") (pinfunction "2_2") (pintype "passive"))
      (node (ref "R9") (pin "1") (pinfunction "1_1") (pintype "passive"))
      (node (ref "VC") (pin "2") (pinfunction "VOUT_2") (pintype "bidirectional"))
    )
    (net (code "43") (name "3.3V_CPUBRD") (class "Default")
      (node (ref "JP10") (pin "3") (pinfunction "3_3") (pintype "passive"))
      (node (ref "JP11") (pin "3") (pinfunction "3_3") (pintype "passive"))
      (node (ref "JP8") (pin "2") (pinfunction "2_2") (pintype "passive"))
    )
    (net (code "44") (name "5V_CPUBRD") (class "Default")
      (node (ref "JP10") (pin "2") (pinfunction "2_2") (pintype "passive"))
      (node (ref "JP11") (pin "2") (pinfunction "2_2") (pintype "passive"))
      (node (ref "JP7") (pin "2") (pinfunction "2_2") (pintype "passive"))
    )
    (net (code "45") (name "GND") (class "Default")
      (node (ref "1.8V_LED") (pin "C") (pinfunction "C_C") (pintype "passive"))
      (node (ref "3.3V_LED") (pin "C") (pinfunction "C_C") (pintype "passive"))
      (node (ref "5V_LED") (pin "C") (pinfunction "C_C") (pintype "passive"))
      (node (ref "C1") (pin "1") (pinfunction "1_1") (pintype "passive"))
      (node (ref "C10") (pin "1") (pinfunction "1_1") (pintype "passive"))
      (node (ref "C11") (pin "-") (pinfunction "-_-") (pintype "passive"))
      (node (ref "C12") (pin "1") (pinfunction "1_1") (pintype "passive"))
      (node (ref "C13") (pin "1") (pinfunction "1_1") (pintype "passive"))
      (node (ref "C14") (pin "-") (pinfunction "-_-") (pintype "passive"))
      (node (ref "C15") (pin "1") (pinfunction "1_1") (pintype "passive"))
      (node (ref "C16") (pin "1") (pinfunction "1_1") (pintype "passive"))
      (node (ref "C17") (pin "1") (pinfunction "1_1") (pintype "passive"))
      (node (ref "C18") (pin "1") (pinfunction "1_1") (pintype "passive"))
      (node (ref "C19") (pin "1") (pinfunction "1_1") (pintype "passive"))
      (node (ref "C2") (pin "1") (pinfunction "1_1") (pintype "passive"))
      (node (ref "C20") (pin "1") (pinfunction "1_1") (pintype "passive"))
      (node (ref "C21") (pin "2") (pinfunction "2_2") (pintype "passive"))
      (node (ref "C22") (pin "2") (pinfunction "2_2") (pintype "passive"))
      (node (ref "C23") (pin "1") (pinfunction "1_1") (pintype "passive"))
      (node (ref "C24") (pin "1") (pinfunction "1_1") (pintype "passive"))
      (node (ref "C25") (pin "2") (pinfunction "2_2") (pintype "passive"))
      (node (ref "C26") (pin "2") (pinfunction "2_2") (pintype "passive"))
      (node (ref "C27") (pin "-") (pinfunction "-_-") (pintype "passive"))
      (node (ref "C28") (pin "-") (pinfunction "-_-") (pintype "passive"))
      (node (ref "C29") (pin "-") (pinfunction "-_-") (pintype "passive"))
      (node (ref "C3") (pin "1") (pinfunction "1_1") (pintype "passive"))
      (node (ref "C30") (pin "-") (pinfunction "-_-") (pintype "passive"))
      (node (ref "C4") (pin "1") (pinfunction "1_1") (pintype "passive"))
      (node (ref "C5") (pin "1") (pinfunction "1_1") (pintype "passive"))
      (node (ref "C6") (pin "1") (pinfunction "1_1") (pintype "passive"))
      (node (ref "C7") (pin "1") (pinfunction "1_1") (pintype "passive"))
      (node (ref "C8") (pin "-") (pinfunction "-_-") (pintype "passive"))
      (node (ref "C9") (pin "-") (pinfunction "-_-") (pintype "passive"))
      (node (ref "CONN1") (pin "GND") (pinfunction "GND_GND") (pintype "bidirectional"))
      (node (ref "IC") (pin "1") (pinfunction "GND0_1") (pintype "bidirectional"))
      (node (ref "IC") (pin "10") (pinfunction "AGND_10") (pintype "bidirectional"))
      (node (ref "IC") (pin "11") (pinfunction "GND2_11") (pintype "bidirectional"))
      (node (ref "IC") (pin "13") (pinfunction "TEST_13") (pintype "bidirectional"))
      (node (ref "IC") (pin "15") (pinfunction "GND3_15") (pintype "bidirectional"))
      (node (ref "IC") (pin "25") (pinfunction "GND4_25") (pintype "bidirectional"))
      (node (ref "IC") (pin "35") (pinfunction "GND5_35") (pintype "bidirectional"))
      (node (ref "IC") (pin "47") (pinfunction "GND6_47") (pintype "bidirectional"))
      (node (ref "IC") (pin "5") (pinfunction "GND1_5") (pintype "bidirectional"))
      (node (ref "IC") (pin "51") (pinfunction "GND7_51") (pintype "bidirectional"))
      (node (ref "JP10") (pin "12") (pinfunction "12_12") (pintype "passive"))
      (node (ref "JP10") (pin "24") (pinfunction "24_24") (pintype "passive"))
      (node (ref "JP10") (pin "5") (pinfunction "5_5") (pintype "passive"))
      (node (ref "JP11") (pin "12") (pinfunction "12_12") (pintype "passive"))
      (node (ref "JP11") (pin "24") (pinfunction "24_24") (pintype "passive"))
      (node (ref "JP11") (pin "5") (pinfunction "5_5") (pintype "passive"))
      (node (ref "JP12") (pin "12") (pinfunction "12_12") (pintype "passive"))
      (node (ref "JP12") (pin "24") (pinfunction "24_24") (pintype "passive"))
      (node (ref "JP13") (pin "12") (pinfunction "12_12") (pintype "passive"))
      (node (ref "JP13") (pin "24") (pinfunction "24_24") (pintype "passive"))
      (node (ref "JTAG") (pin "10") (pinfunction "KL_10") (pintype "passive"))
      (node (ref "JTAG") (pin "12") (pinfunction "KL_12") (pintype "passive"))
      (node (ref "JTAG") (pin "14") (pinfunction "KL_14") (pintype "passive"))
      (node (ref "JTAG") (pin "16") (pinfunction "KL_16") (pintype "passive"))
      (node (ref "JTAG") (pin "18") (pinfunction "KL_18") (pintype "passive"))
      (node (ref "JTAG") (pin "20") (pinfunction "KL_20") (pintype "passive"))
      (node (ref "JTAG") (pin "4") (pinfunction "KL_4") (pintype "passive"))
      (node (ref "JTAG") (pin "6") (pinfunction "KL_6") (pintype "passive"))
      (node (ref "JTAG") (pin "8") (pinfunction "KL_8") (pintype "passive"))
      (node (ref "LS1") (pin "10") (pinfunction "A8_10") (pintype "bidirectional"))
      (node (ref "LS1") (pin "11") (pinfunction "GND_11") (pintype "bidirectional"))
      (node (ref "LS1") (pin "12") (pinfunction "GND2_12") (pintype "bidirectional"))
      (node (ref "LS1") (pin "13") (pinfunction "GND3_13") (pintype "bidirectional"))
      (node (ref "LS1") (pin "6") (pinfunction "A4_6") (pintype "bidirectional"))
      (node (ref "LS1") (pin "7") (pinfunction "A5_7") (pintype "bidirectional"))
      (node (ref "LS1") (pin "8") (pinfunction "A6_8") (pintype "bidirectional"))
      (node (ref "LS1") (pin "9") (pinfunction "A7_9") (pintype "bidirectional"))
      (node (ref "LS2") (pin "10") (pinfunction "A8_10") (pintype "bidirectional"))
      (node (ref "LS2") (pin "11") (pinfunction "GND_11") (pintype "bidirectional"))
      (node (ref "LS2") (pin "12") (pinfunction "GND2_12") (pintype "bidirectional"))
      (node (ref "LS2") (pin "13") (pinfunction "GND3_13") (pintype "bidirectional"))
      (node (ref "LS2") (pin "2") (pinfunction "DIR_2") (pintype "bidirectional"))
      (node (ref "LS2") (pin "22") (pinfunction "OE_22") (pintype "bidirectional"))
      (node (ref "LS2") (pin "6") (pinfunction "A4_6") (pintype "bidirectional"))
      (node (ref "LS2") (pin "7") (pinfunction "A5_7") (pintype "bidirectional"))
      (node (ref "LS2") (pin "8") (pinfunction "A6_8") (pintype "bidirectional"))
      (node (ref "LS2") (pin "9") (pinfunction "A7_9") (pintype "bidirectional"))
      (node (ref "LS3") (pin "10") (pinfunction "A8_10") (pintype "bidirectional"))
      (node (ref "LS3") (pin "11") (pinfunction "GND_11") (pintype "bidirectional"))
      (node (ref "LS3") (pin "12") (pinfunction "GND2_12") (pintype "bidirectional"))
      (node (ref "LS3") (pin "13") (pinfunction "GND3_13") (pintype "bidirectional"))
      (node (ref "LS3") (pin "4") (pinfunction "A2_4") (pintype "bidirectional"))
      (node (ref "LS3") (pin "5") (pinfunction "A3_5") (pintype "bidirectional"))
      (node (ref "LS3") (pin "6") (pinfunction "A4_6") (pintype "bidirectional"))
      (node (ref "LS3") (pin "7") (pinfunction "A5_7") (pintype "bidirectional"))
      (node (ref "LS3") (pin "8") (pinfunction "A6_8") (pintype "bidirectional"))
      (node (ref "LS3") (pin "9") (pinfunction "A7_9") (pintype "bidirectional"))
      (node (ref "LS4") (pin "10") (pinfunction "A8_10") (pintype "bidirectional"))
      (node (ref "LS4") (pin "11") (pinfunction "GND_11") (pintype "bidirectional"))
      (node (ref "LS4") (pin "12") (pinfunction "GND2_12") (pintype "bidirectional"))
      (node (ref "LS4") (pin "13") (pinfunction "GND3_13") (pintype "bidirectional"))
      (node (ref "LS4") (pin "4") (pinfunction "A2_4") (pintype "bidirectional"))
      (node (ref "LS4") (pin "5") (pinfunction "A3_5") (pintype "bidirectional"))
      (node (ref "LS4") (pin "6") (pinfunction "A4_6") (pintype "bidirectional"))
      (node (ref "LS4") (pin "7") (pinfunction "A5_7") (pintype "bidirectional"))
      (node (ref "LS4") (pin "8") (pinfunction "A6_8") (pintype "bidirectional"))
      (node (ref "LS4") (pin "9") (pinfunction "A7_9") (pintype "bidirectional"))
      (node (ref "LS5") (pin "4") (pinfunction "GND_4") (pintype "passive"))
      (node (ref "LS5") (pin "5") (pinfunction "DIR_5") (pintype "input"))
      (node (ref "LS6") (pin "4") (pinfunction "GND_4") (pintype "passive"))
      (node (ref "MEM") (pin "5") (pinfunction "GND_5") (pintype "bidirectional"))
      (node (ref "MEM") (pin "7") (pinfunction "DC_7") (pintype "bidirectional"))
      (node (ref "PROG") (pin "1") (pinfunction "1_1") (pintype "passive"))
      (node (ref "PWR_LED") (pin "C") (pinfunction "C_C") (pintype "passive"))
      (node (ref "Q1") (pin "1") (pinfunction "G_1") (pintype "passive"))
      (node (ref "Q2") (pin "1") (pinfunction "G_1") (pintype "passive"))
      (node (ref "Q3") (pin "2") (pinfunction "E_2") (pintype "bidirectional"))
      (node (ref "Q4") (pin "2") (pinfunction "E_2") (pintype "bidirectional"))
      (node (ref "Q5") (pin "2") (pinfunction "E_2") (pintype "bidirectional"))
      (node (ref "R14") (pin "2") (pinfunction "2_2") (pintype "passive"))
      (node (ref "R15") (pin "2") (pinfunction "2_2") (pintype "passive"))
      (node (ref "R6") (pin "1") (pinfunction "1_1") (pintype "passive"))
      (node (ref "R8") (pin "1") (pinfunction "1_1") (pintype "passive"))
      (node (ref "T1") (pin "E") (pinfunction "E_E") (pintype "passive"))
      (node (ref "TARGET_SW") (pin "3") (pinfunction "3_3") (pintype "passive"))
      (node (ref "TVS1") (pin "1") (pinfunction "1_1") (pintype "passive"))
      (node (ref "TVS2") (pin "1") (pinfunction "1_1") (pintype "passive"))
      (node (ref "U3") (pin "4") (pinfunction "GND_4") (pintype "bidirectional"))
      (node (ref "U3") (pin "PAD") (pinfunction "EP_PAD") (pintype "bidirectional"))
      (node (ref "U4") (pin "4") (pinfunction "GND_4") (pintype "bidirectional"))
      (node (ref "U4") (pin "PAD") (pinfunction "EP_PAD") (pintype "bidirectional"))
      (node (ref "USER_BTN1") (pin "1") (pintype "bidirectional"))
      (node (ref "USER_BTN1") (pin "2") (pintype "bidirectional"))
      (node (ref "USER_BTN2") (pin "1") (pintype "bidirectional"))
      (node (ref "USER_BTN2") (pin "2") (pintype "bidirectional"))
      (node (ref "USER_BTN3") (pin "1") (pintype "bidirectional"))
      (node (ref "USER_BTN3") (pin "2") (pintype "bidirectional"))
      (node (ref "VC") (pin "1") (pinfunction "GND_1") (pintype "bidirectional"))
      (node (ref "VME_GND") (pin "P$1") (pinfunction "1_P$1") (pintype "passive"))
      (node (ref "VMO_GND") (pin "P$1") (pinfunction "1_P$1") (pintype "passive"))
    )
    (net (code "46") (name "I2C_SCL") (class "Default")
      (node (ref "JP12") (pin "14") (pinfunction "14_14") (pintype "passive"))
      (node (ref "JP13") (pin "14") (pinfunction "14_14") (pintype "passive"))
    )
    (net (code "47") (name "I2C_SDA") (class "Default")
      (node (ref "JP12") (pin "13") (pinfunction "13_13") (pintype "passive"))
      (node (ref "JP13") (pin "13") (pinfunction "13_13") (pintype "passive"))
    )
    (net (code "48") (name "N$27") (class "Default")
      (node (ref "JP10") (pin "6") (pinfunction "6_6") (pintype "passive"))
      (node (ref "JP11") (pin "6") (pinfunction "6_6") (pintype "passive"))
    )
    (net (code "49") (name "N$28") (class "Default")
      (node (ref "JP10") (pin "7") (pinfunction "7_7") (pintype "passive"))
      (node (ref "JP11") (pin "7") (pinfunction "7_7") (pintype "passive"))
    )
    (net (code "50") (name "N$29") (class "Default")
      (node (ref "JP10") (pin "8") (pinfunction "8_8") (pintype "passive"))
      (node (ref "JP11") (pin "8") (pinfunction "8_8") (pintype "passive"))
    )
    (net (code "51") (name "N$30") (class "Default")
      (node (ref "JP10") (pin "9") (pinfunction "9_9") (pintype "passive"))
      (node (ref "JP11") (pin "9") (pinfunction "9_9") (pintype "passive"))
    )
    (net (code "52") (name "N$31") (class "Default")
      (node (ref "JP10") (pin "10") (pinfunction "10_10") (pintype "passive"))
      (node (ref "JP11") (pin "10") (pinfunction "10_10") (pintype "passive"))
    )
    (net (code "53") (name "N$32") (class "Default")
      (node (ref "JP10") (pin "11") (pinfunction "11_11") (pintype "passive"))
      (node (ref "JP11") (pin "11") (pinfunction "11_11") (pintype "passive"))
    )
    (net (code "54") (name "N$37") (class "Default")
      (node (ref "JP10") (pin "16") (pinfunction "16_16") (pintype "passive"))
      (node (ref "JP11") (pin "16") (pinfunction "16_16") (pintype "passive"))
    )
    (net (code "55") (name "N$38") (class "Default")
      (node (ref "JP10") (pin "17") (pinfunction "17_17") (pintype "passive"))
      (node (ref "JP11") (pin "17") (pinfunction "17_17") (pintype "passive"))
    )
    (net (code "56") (name "N$42") (class "Default")
      (node (ref "JP10") (pin "21") (pinfunction "21_21") (pintype "passive"))
      (node (ref "JP11") (pin "21") (pinfunction "21_21") (pintype "passive"))
    )
    (net (code "57") (name "N$43") (class "Default")
      (node (ref "JP10") (pin "22") (pinfunction "22_22") (pintype "passive"))
      (node (ref "JP11") (pin "22") (pinfunction "22_22") (pintype "passive"))
    )
    (net (code "58") (name "N$44") (class "Default")
      (node (ref "JP10") (pin "23") (pinfunction "23_23") (pintype "passive"))
      (node (ref "JP11") (pin "23") (pinfunction "23_23") (pintype "passive"))
    )
    (net (code "59") (name "N$56") (class "Default")
      (node (ref "JP12") (pin "5") (pinfunction "5_5") (pintype "passive"))
      (node (ref "JP13") (pin "5") (pinfunction "5_5") (pintype "passive"))
    )
    (net (code "60") (name "N$57") (class "Default")
      (node (ref "JP12") (pin "6") (pinfunction "6_6") (pintype "passive"))
      (node (ref "JP13") (pin "6") (pinfunction "6_6") (pintype "passive"))
    )
    (net (code "61") (name "N$58") (class "Default")
      (node (ref "JP12") (pin "7") (pinfunction "7_7") (pintype "passive"))
      (node (ref "JP13") (pin "7") (pinfunction "7_7") (pintype "passive"))
    )
    (net (code "62") (name "N$70") (class "Default")
      (node (ref "JP12") (pin "19") (pinfunction "19_19") (pintype "passive"))
      (node (ref "JP13") (pin "19") (pinfunction "19_19") (pintype "passive"))
    )
    (net (code "63") (name "Net-(1.8V_LED-PadA)") (class "Default")
      (node (ref "1.8V_LED") (pin "A") (pinfunction "A_A") (pintype "passive"))
      (node (ref "R18") (pin "1") (pinfunction "1_1") (pintype "passive"))
    )
    (net (code "64") (name "Net-(3.3V_LED-PadA)") (class "Default")
      (node (ref "3.3V_LED") (pin "A") (pinfunction "A_A") (pintype "passive"))
      (node (ref "R17") (pin "1") (pinfunction "1_1") (pintype "passive"))
    )
    (net (code "65") (name "Net-(5V_LED-PadA)") (class "Default")
      (node (ref "5V_LED") (pin "A") (pinfunction "A_A") (pintype "passive"))
      (node (ref "R16") (pin "1") (pinfunction "1_1") (pintype "passive"))
    )
    (net (code "66") (name "Net-(F1-2)") (class "Default")
      (node (ref "F1") (pin "P$2") (pinfunction "2_P$2") (pintype "passive"))
      (node (ref "Q1") (pin "3") (pinfunction "D_3") (pintype "passive"))
      (node (ref "TVS1") (pin "2") (pinfunction "2_2") (pintype "passive"))
    )
    (net (code "67") (name "Net-(F2-1)") (class "Default")
      (node (ref "F2") (pin "P$1") (pinfunction "1_P$1") (pintype "passive"))
      (node (ref "JP_PROTECTION") (pin "5") (pinfunction "5_5") (pintype "passive"))
    )
    (net (code "68") (name "Net-(F2-2)") (class "Default")
      (node (ref "F2") (pin "P$2") (pinfunction "2_P$2") (pintype "passive"))
      (node (ref "F3") (pin "P$2") (pinfunction "2_P$2") (pintype "passive"))
      (node (ref "F4") (pin "P$2") (pinfunction "2_P$2") (pintype "passive"))
      (node (ref "Q2") (pin "3") (pinfunction "D_3") (pintype "passive"))
      (node (ref "TVS2") (pin "2") (pinfunction "2_2") (pintype "passive"))
    )
    (net (code "69") (name "Net-(F3-1)") (class "Default")
      (node (ref "F3") (pin "P$1") (pinfunction "1_P$1") (pintype "passive"))
      (node (ref "JP_PROTECTION") (pin "3") (pinfunction "3_3") (pintype "passive"))
    )
    (net (code "70") (name "Net-(F4-1)") (class "Default")
      (node (ref "F4") (pin "P$1") (pinfunction "1_P$1") (pintype "passive"))
      (node (ref "JP_PROTECTION") (pin "1") (pinfunction "1_1") (pintype "passive"))
    )
    (net (code "71") (name "Net-(IC-OSC0)") (class "Default")
      (node (ref "C22") (pin "1") (pinfunction "1_1") (pintype "passive"))
      (node (ref "IC") (pin "3") (pinfunction "OSC0_3") (pintype "bidirectional"))
      (node (ref "X1") (pin "2") (pinfunction "X2_2") (pintype "bidirectional"))
    )
    (net (code "72") (name "Net-(IC-OSCI)") (class "Default")
      (node (ref "C21") (pin "1") (pinfunction "1_1") (pintype "passive"))
      (node (ref "IC") (pin "2") (pinfunction "OSCI_2") (pintype "bidirectional"))
      (node (ref "X1") (pin "1") (pinfunction "X1_1") (pintype "bidirectional"))
    )
    (net (code "73") (name "Net-(IC-REF)") (class "Default")
      (node (ref "IC") (pin "6") (pinfunction "REF_6") (pintype "bidirectional"))
      (node (ref "R8") (pin "2") (pinfunction "2_2") (pintype "passive"))
    )
    (net (code "74") (name "Net-(IC-RESET#)") (class "Default")
      (node (ref "IC") (pin "14") (pinfunction "RESET#_14") (pintype "bidirectional"))
      (node (ref "R9") (pin "2") (pinfunction "2_2") (pintype "passive"))
    )
    (net (code "75") (name "Net-(IC-VPHY)") (class "Default")
      (node (ref "C11") (pin "+") (pinfunction "+_+") (pintype "passive"))
      (node (ref "C12") (pin "2") (pinfunction "2_2") (pintype "passive"))
      (node (ref "IC") (pin "4") (pinfunction "VPHY_4") (pintype "bidirectional"))
      (node (ref "L2") (pin "1") (pinfunction "1_1") (pintype "passive"))
    )
    (net (code "76") (name "Net-(IC-VPLL)") (class "Default")
      (node (ref "C10") (pin "2") (pinfunction "2_2") (pintype "passive"))
      (node (ref "C9") (pin "+") (pinfunction "+_+") (pintype "passive"))
      (node (ref "IC") (pin "9") (pinfunction "VPLL_9") (pintype "bidirectional"))
      (node (ref "L1") (pin "1") (pinfunction "1_1") (pintype "passive"))
    )
    (net (code "77") (name "Net-(JP12-Pad8)") (class "Default")
      (node (ref "JP12") (pin "8") (pinfunction "8_8") (pintype "passive"))
      (node (ref "JP13") (pin "8") (pinfunction "8_8") (pintype "passive"))
      (node (ref "JTAG_SW") (pin "8") (pinfunction "8_8") (pintype "passive"))
    )
    (net (code "78") (name "Net-(JP12-Pad9)") (class "Default")
      (node (ref "JP12") (pin "9") (pinfunction "9_9") (pintype "passive"))
      (node (ref "JP13") (pin "9") (pinfunction "9_9") (pintype "passive"))
      (node (ref "JTAG_SW") (pin "7") (pinfunction "7_7") (pintype "passive"))
    )
    (net (code "79") (name "Net-(JP12-Pad10)") (class "Default")
      (node (ref "JP12") (pin "10") (pinfunction "10_10") (pintype "passive"))
      (node (ref "JP13") (pin "10") (pinfunction "10_10") (pintype "passive"))
      (node (ref "JTAG_SW") (pin "6") (pinfunction "6_6") (pintype "passive"))
    )
    (net (code "80") (name "Net-(JP12-Pad11)") (class "Default")
      (node (ref "JP12") (pin "11") (pinfunction "11_11") (pintype "passive"))
      (node (ref "JP13") (pin "11") (pinfunction "11_11") (pintype "passive"))
      (node (ref "JTAG_SW") (pin "5") (pinfunction "5_5") (pintype "passive"))
    )
    (net (code "81") (name "Net-(JP12-Pad15)") (class "Default")
      (node (ref "JP12") (pin "15") (pinfunction "15_15") (pintype "passive"))
      (node (ref "JP13") (pin "15") (pinfunction "15_15") (pintype "passive"))
      (node (ref "UART1_SW") (pin "8") (pinfunction "8_8") (pintype "passive"))
    )
    (net (code "82") (name "Net-(JP12-Pad16)") (class "Default")
      (node (ref "JP12") (pin "16") (pinfunction "16_16") (pintype "passive"))
      (node (ref "JP13") (pin "16") (pinfunction "16_16") (pintype "passive"))
      (node (ref "UART1_SW") (pin "7") (pinfunction "7_7") (pintype "passive"))
    )
    (net (code "83") (name "Net-(JP12-Pad17)") (class "Default")
      (node (ref "JP12") (pin "17") (pinfunction "17_17") (pintype "passive"))
      (node (ref "JP13") (pin "17") (pinfunction "17_17") (pintype "passive"))
      (node (ref "UART1_SW") (pin "6") (pinfunction "6_6") (pintype "passive"))
    )
    (net (code "84") (name "Net-(JP12-Pad18)") (class "Default")
      (node (ref "JP12") (pin "18") (pinfunction "18_18") (pintype "passive"))
      (node (ref "JP13") (pin "18") (pinfunction "18_18") (pintype "passive"))
      (node (ref "UART1_SW") (pin "5") (pinfunction "5_5") (pintype "passive"))
    )
    (net (code "85") (name "Net-(PWR_LED-PadA)") (class "Default")
      (node (ref "PWR_LED") (pin "A") (pinfunction "A_A") (pintype "passive"))
      (node (ref "R7") (pin "1") (pinfunction "1_1") (pintype "passive"))
    )
    (net (code "86") (name "Net-(Q3-B)") (class "Default")
      (node (ref "LED_SW") (pin "6") (pinfunction "6_6") (pintype "passive"))
      (node (ref "Q3") (pin "1") (pinfunction "B_1") (pintype "bidirectional"))
    )
    (net (code "87") (name "Net-(Q3-C)") (class "Default")
      (node (ref "Q3") (pin "3") (pinfunction "C_3") (pintype "bidirectional"))
      (node (ref "R21") (pin "1") (pinfunction "1_1") (pintype "passive"))
    )
    (net (code "88") (name "Net-(Q4-B)") (class "Default")
      (node (ref "LED_SW") (pin "5") (pinfunction "5_5") (pintype "passive"))
      (node (ref "Q4") (pin "1") (pinfunction "B_1") (pintype "bidirectional"))
    )
    (net (code "89") (name "Net-(Q4-C)") (class "Default")
      (node (ref "Q4") (pin "3") (pinfunction "C_3") (pintype "bidirectional"))
      (node (ref "R22") (pin "1") (pinfunction "1_1") (pintype "passive"))
    )
    (net (code "90") (name "Net-(Q5-B)") (class "Default")
      (node (ref "LED_SW") (pin "4") (pinfunction "4_4") (pintype "passive"))
      (node (ref "Q5") (pin "1") (pinfunction "B_1") (pintype "bidirectional"))
    )
    (net (code "91") (name "Net-(Q5-C)") (class "Default")
      (node (ref "Q5") (pin "3") (pinfunction "C_3") (pintype "bidirectional"))
      (node (ref "R23") (pin "1") (pinfunction "1_1") (pintype "passive"))
    )
    (net (code "92") (name "Net-(R2-Pad1)") (class "Default")
      (node (ref "R2") (pin "1") (pinfunction "1_1") (pintype "passive"))
      (node (ref "TARGET_PRESENT") (pin "A") (pinfunction "A_A") (pintype "passive"))
    )
    (net (code "93") (name "Net-(R3-Pad1)") (class "Default")
      (node (ref "R3") (pin "1") (pinfunction "1_1") (pintype "passive"))
      (node (ref "TX") (pin "A") (pinfunction "A_A") (pintype "passive"))
    )
    (net (code "94") (name "Net-(R4-Pad1)") (class "Default")
      (node (ref "R4") (pin "1") (pinfunction "1_1") (pintype "passive"))
      (node (ref "RX") (pin "A") (pinfunction "A_A") (pintype "passive"))
    )
    (net (code "95") (name "Net-(R5-Pad1)") (class "Default")
      (node (ref "R5") (pin "1") (pinfunction "1_1") (pintype "passive"))
      (node (ref "R6") (pin "2") (pinfunction "2_2") (pintype "passive"))
      (node (ref "T1") (pin "B") (pinfunction "B_B") (pintype "passive"))
    )
    (net (code "96") (name "Net-(R21-Pad2)") (class "Default")
      (node (ref "R21") (pin "2") (pinfunction "2_2") (pintype "passive"))
      (node (ref "USER_LED3") (pin "C") (pinfunction "C_C") (pintype "passive"))
    )
    (net (code "97") (name "Net-(R22-Pad2)") (class "Default")
      (node (ref "R22") (pin "2") (pinfunction "2_2") (pintype "passive"))
      (node (ref "USER_LED2") (pin "C") (pinfunction "C_C") (pintype "passive"))
    )
    (net (code "98") (name "Net-(R23-Pad2)") (class "Default")
      (node (ref "R23") (pin "2") (pinfunction "2_2") (pintype "passive"))
      (node (ref "USER_LED1") (pin "C") (pinfunction "C_C") (pintype "passive"))
    )
    (net (code "99") (name "Net-(U3-NR)") (class "Default")
      (node (ref "C25") (pin "1") (pinfunction "1_1") (pintype "passive"))
      (node (ref "U3") (pin "7") (pinfunction "NR_7") (pintype "bidirectional"))
    )
    (net (code "100") (name "Net-(U3-SENSE{slash}ADJ)") (class "Default")
      (node (ref "R14") (pin "1") (pinfunction "1_1") (pintype "passive"))
      (node (ref "R19") (pin "2") (pinfunction "2_2") (pintype "passive"))
      (node (ref "U3") (pin "3") (pinfunction "SENSE/ADJ_3") (pintype "bidirectional"))
    )
    (net (code "101") (name "Net-(U4-NR)") (class "Default")
      (node (ref "C26") (pin "1") (pinfunction "1_1") (pintype "passive"))
      (node (ref "U4") (pin "7") (pinfunction "NR_7") (pintype "bidirectional"))
    )
    (net (code "102") (name "Net-(U4-SENSE{slash}ADJ)") (class "Default")
      (node (ref "R15") (pin "1") (pinfunction "1_1") (pintype "passive"))
      (node (ref "R20") (pin "2") (pinfunction "2_2") (pintype "passive"))
      (node (ref "U4") (pin "3") (pinfunction "SENSE/ADJ_3") (pintype "bidirectional"))
    )
    (net (code "103") (name "Net-(VC-VIN)") (class "Default")
      (node (ref "C15") (pin "2") (pinfunction "2_2") (pintype "passive"))
      (node (ref "CONN1") (pin "VUSB") (pinfunction "VUSB_VUSB") (pintype "bidirectional"))
      (node (ref "VC") (pin "3") (pinfunction "VIN_3") (pintype "bidirectional"))
    )
    (net (code "104") (name "SPI_SCK") (class "Default")
      (node (ref "JP12") (pin "3") (pinfunction "3_3") (pintype "passive"))
      (node (ref "JP13") (pin "3") (pinfunction "3_3") (pintype "passive"))
    )
    (net (code "105") (name "SPI_SDI") (class "Default")
      (node (ref "JP12") (pin "1") (pinfunction "1_1") (pintype "passive"))
      (node (ref "JP13") (pin "1") (pinfunction "1_1") (pintype "passive"))
    )
    (net (code "106") (name "SPI_SDO") (class "Default")
      (node (ref "JP12") (pin "2") (pinfunction "2_2") (pintype "passive"))
      (node (ref "JP13") (pin "2") (pinfunction "2_2") (pintype "passive"))
    )
    (net (code "107") (name "TCK-1") (class "Default")
      (node (ref "JTAG") (pin "9") (pinfunction "KL_9") (pintype "passive"))
      (node (ref "JTAG_SW") (pin "4") (pinfunction "4_4") (pintype "passive"))
      (node (ref "LS1") (pin "19") (pinfunction "B3_19") (pintype "bidirectional"))
    )
    (net (code "108") (name "TDI-1") (class "Default")
      (node (ref "JTAG") (pin "5") (pinfunction "KL_5") (pintype "passive"))
      (node (ref "JTAG_SW") (pin "3") (pinfunction "3_3") (pintype "passive"))
      (node (ref "LS1") (pin "21") (pinfunction "B1_21") (pintype "bidirectional"))
    )
    (net (code "109") (name "TDO{slash}DI-1") (class "Default")
      (node (ref "JTAG") (pin "13") (pinfunction "KL_13") (pintype "passive"))
      (node (ref "JTAG_SW") (pin "2") (pinfunction "2_2") (pintype "passive"))
      (node (ref "LS2") (pin "21") (pinfunction "B1_21") (pintype "bidirectional"))
    )
    (net (code "110") (name "TMS-1") (class "Default")
      (node (ref "JTAG") (pin "7") (pinfunction "KL_7") (pintype "passive"))
      (node (ref "JTAG_SW") (pin "1") (pinfunction "1_1") (pintype "passive"))
      (node (ref "LS1") (pin "20") (pinfunction "B2_20") (pintype "bidirectional"))
    )
    (net (code "111") (name "UART1_RX") (class "Default")
      (node (ref "LS6") (pin "7") (pinfunction "B1_7") (pintype "bidirectional"))
      (node (ref "UART1_SW") (pin "1") (pinfunction "1_1") (pintype "passive"))
    )
    (net (code "112") (name "UART1_TX") (class "Default")
      (node (ref "LS5") (pin "7") (pinfunction "B1_7") (pintype "bidirectional"))
      (node (ref "UART1_SW") (pin "2") (pinfunction "2_2") (pintype "passive"))
    )
    (net (code "113") (name "UART2_RX") (class "Default")
      (node (ref "JP12") (pin "20") (pinfunction "20_20") (pintype "passive"))
      (node (ref "JP13") (pin "20") (pinfunction "20_20") (pintype "passive"))
    )
    (net (code "114") (name "UART2_TX") (class "Default")
      (node (ref "JP12") (pin "21") (pinfunction "21_21") (pintype "passive"))
      (node (ref "JP13") (pin "21") (pinfunction "21_21") (pintype "passive"))
    )
    (net (code "115") (name "USER_BTN1") (class "Default")
      (node (ref "JP10") (pin "18") (pinfunction "18_18") (pintype "passive"))
      (node (ref "JP11") (pin "18") (pinfunction "18_18") (pintype "passive"))
      (node (ref "USER_BTN1") (pin "3") (pintype "bidirectional"))
      (node (ref "USER_BTN1") (pin "4") (pintype "bidirectional"))
    )
    (net (code "116") (name "USER_BTN2") (class "Default")
      (node (ref "JP10") (pin "19") (pinfunction "19_19") (pintype "passive"))
      (node (ref "JP11") (pin "19") (pinfunction "19_19") (pintype "passive"))
      (node (ref "USER_BTN2") (pin "3") (pintype "bidirectional"))
      (node (ref "USER_BTN2") (pin "4") (pintype "bidirectional"))
    )
    (net (code "117") (name "USER_BTN3") (class "Default")
      (node (ref "JP10") (pin "20") (pinfunction "20_20") (pintype "passive"))
      (node (ref "JP11") (pin "20") (pinfunction "20_20") (pintype "passive"))
      (node (ref "USER_BTN3") (pin "3") (pintype "bidirectional"))
      (node (ref "USER_BTN3") (pin "4") (pintype "bidirectional"))
    )
    (net (code "118") (name "USER_LED1") (class "Default")
      (node (ref "JP10") (pin "13") (pinfunction "13_13") (pintype "passive"))
      (node (ref "JP11") (pin "13") (pinfunction "13_13") (pintype "passive"))
      (node (ref "LED_SW") (pin "3") (pinfunction "3_3") (pintype "passive"))
    )
    (net (code "119") (name "USER_LED2") (class "Default")
      (node (ref "JP10") (pin "14") (pinfunction "14_14") (pintype "passive"))
      (node (ref "JP11") (pin "14") (pinfunction "14_14") (pintype "passive"))
      (node (ref "LED_SW") (pin "2") (pinfunction "2_2") (pintype "passive"))
    )
    (net (code "120") (name "USER_LED3") (class "Default")
      (node (ref "JP10") (pin "15") (pinfunction "15_15") (pintype "passive"))
      (node (ref "JP11") (pin "15") (pinfunction "15_15") (pintype "passive"))
      (node (ref "LED_SW") (pin "1") (pinfunction "1_1") (pintype "passive"))
    )
    (net (code "121") (name "V_CPU") (class "Default")
      (node (ref "JP10") (pin "1") (pinfunction "1_1") (pintype "passive"))
      (node (ref "JP11") (pin "1") (pinfunction "1_1") (pintype "passive"))
      (node (ref "TARGET_SW") (pin "1") (pinfunction "1_1") (pintype "passive"))
    )
    (net (code "122") (name "unconnected-(CONN1B-USBID-PadID)") (class "Default")
      (node (ref "CONN1") (pin "ID") (pinfunction "USBID_ID") (pintype "bidirectional"))
    )
    (net (code "123") (name "unconnected-(IC-ACBUS4{slash}TXLED#{slash}GPIOH4-Pad30)") (class "Default")
      (node (ref "IC") (pin "30") (pinfunction "ACBUS4/TXLED#/GPIOH4_30") (pintype "bidirectional"))
    )
    (net (code "124") (name "unconnected-(IC-ACBUS5{slash}GPIOH5-Pad32)") (class "Default")
      (node (ref "IC") (pin "32") (pinfunction "ACBUS5/GPIOH5_32") (pintype "bidirectional"))
    )
    (net (code "125") (name "unconnected-(IC-ACBUS6{slash}GPIOH6-Pad33)") (class "Default")
      (node (ref "IC") (pin "33") (pinfunction "ACBUS6/GPIOH6_33") (pintype "bidirectional"))
    )
    (net (code "126") (name "unconnected-(IC-ACBUS7{slash}GPIOH7-Pad34)") (class "Default")
      (node (ref "IC") (pin "34") (pinfunction "ACBUS7/GPIOH7_34") (pintype "bidirectional"))
    )
    (net (code "127") (name "unconnected-(IC-BCBUS0{slash}GPIOH1-Pad48)") (class "Default")
      (node (ref "IC") (pin "48") (pinfunction "BCBUS0/GPIOH1_48") (pintype "bidirectional"))
    )
    (net (code "128") (name "unconnected-(IC-BCBUS1{slash}GPIOH2-Pad52)") (class "Default")
      (node (ref "IC") (pin "52") (pinfunction "BCBUS1/GPIOH2_52") (pintype "bidirectional"))
    )
    (net (code "129") (name "unconnected-(IC-BCBUS2-Pad53)") (class "Default")
      (node (ref "IC") (pin "53") (pinfunction "BCBUS2_53") (pintype "bidirectional"))
    )
    (net (code "130") (name "unconnected-(IC-BCBUS5{slash}GPIOH5-Pad57)") (class "Default")
      (node (ref "IC") (pin "57") (pinfunction "BCBUS5/GPIOH5_57") (pintype "bidirectional"))
    )
    (net (code "131") (name "unconnected-(IC-BCBUS6{slash}GPIOH6-Pad58)") (class "Default")
      (node (ref "IC") (pin "58") (pinfunction "BCBUS6/GPIOH6_58") (pintype "bidirectional"))
    )
    (net (code "132") (name "unconnected-(IC-BCBUS7{slash}GPIOH7-Pad59)") (class "Default")
      (node (ref "IC") (pin "59") (pinfunction "BCBUS7/GPIOH7_59") (pintype "bidirectional"))
    )
    (net (code "133") (name "unconnected-(IC-BDBUS4{slash}DTR#{slash}GPIOL0-Pad43)") (class "Default")
      (node (ref "IC") (pin "43") (pinfunction "BDBUS4/DTR#/GPIOL0_43") (pintype "bidirectional"))
    )
    (net (code "134") (name "unconnected-(IC-BDBUS5{slash}DSR#{slash}GPIOL1-Pad44)") (class "Default")
      (node (ref "IC") (pin "44") (pinfunction "BDBUS5/DSR#/GPIOL1_44") (pintype "bidirectional"))
    )
    (net (code "135") (name "unconnected-(IC-BDBUS6{slash}DCD#{slash}GPIOL2-Pad45)") (class "Default")
      (node (ref "IC") (pin "45") (pinfunction "BDBUS6/DCD#/GPIOL2_45") (pintype "bidirectional"))
    )
    (net (code "136") (name "unconnected-(IC-BDBUS7{slash}RI#{slash}GPIOL3-Pad46)") (class "Default")
      (node (ref "IC") (pin "46") (pinfunction "BDBUS7/RI#/GPIOL3_46") (pintype "bidirectional"))
    )
    (net (code "137") (name "unconnected-(IC-PWREN#-Pad60)") (class "Default")
      (node (ref "IC") (pin "60") (pinfunction "PWREN#_60") (pintype "bidirectional"))
    )
    (net (code "138") (name "unconnected-(IC-SUSPEND#-Pad36)") (class "Default")
      (node (ref "IC") (pin "36") (pinfunction "SUSPEND#_36") (pintype "bidirectional"))
    )
    (net (code "139") (name "unconnected-(JTAGI-KL-Pad17)") (class "Default")
      (node (ref "JTAG") (pin "17") (pinfunction "KL_17") (pintype "passive"))
    )
    (net (code "140") (name "unconnected-(JTAGK-KL-Pad19)") (class "Default")
      (node (ref "JTAG") (pin "19") (pinfunction "KL_19") (pintype "passive"))
    )
    (net (code "141") (name "unconnected-(LS1-B4-Pad18)") (class "Default")
      (node (ref "LS1") (pin "18") (pinfunction "B4_18") (pintype "bidirectional"))
    )
    (net (code "142") (name "unconnected-(LS1-B5-Pad17)") (class "Default")
      (node (ref "LS1") (pin "17") (pinfunction "B5_17") (pintype "bidirectional"))
    )
    (net (code "143") (name "unconnected-(LS1-B6-Pad16)") (class "Default")
      (node (ref "LS1") (pin "16") (pinfunction "B6_16") (pintype "bidirectional"))
    )
    (net (code "144") (name "unconnected-(LS1-B7-Pad15)") (class "Default")
      (node (ref "LS1") (pin "15") (pinfunction "B7_15") (pintype "bidirectional"))
    )
    (net (code "145") (name "unconnected-(LS1-B8-Pad14)") (class "Default")
      (node (ref "LS1") (pin "14") (pinfunction "B8_14") (pintype "bidirectional"))
    )
    (net (code "146") (name "unconnected-(LS2-B4-Pad18)") (class "Default")
      (node (ref "LS2") (pin "18") (pinfunction "B4_18") (pintype "bidirectional"))
    )
    (net (code "147") (name "unconnected-(LS2-B5-Pad17)") (class "Default")
      (node (ref "LS2") (pin "17") (pinfunction "B5_17") (pintype "bidirectional"))
    )
    (net (code "148") (name "unconnected-(LS2-B6-Pad16)") (class "Default")
      (node (ref "LS2") (pin "16") (pinfunction "B6_16") (pintype "bidirectional"))
    )
    (net (code "149") (name "unconnected-(LS2-B7-Pad15)") (class "Default")
      (node (ref "LS2") (pin "15") (pinfunction "B7_15") (pintype "bidirectional"))
    )
    (net (code "150") (name "unconnected-(LS2-B8-Pad14)") (class "Default")
      (node (ref "LS2") (pin "14") (pinfunction "B8_14") (pintype "bidirectional"))
    )
    (net (code "151") (name "unconnected-(LS3-B2-Pad20)") (class "Default")
      (node (ref "LS3") (pin "20") (pinfunction "B2_20") (pintype "bidirectional"))
    )
    (net (code "152") (name "unconnected-(LS3-B3-Pad19)") (class "Default")
      (node (ref "LS3") (pin "19") (pinfunction "B3_19") (pintype "bidirectional"))
    )
    (net (code "153") (name "unconnected-(LS3-B4-Pad18)") (class "Default")
      (node (ref "LS3") (pin "18") (pinfunction "B4_18") (pintype "bidirectional"))
    )
    (net (code "154") (name "unconnected-(LS3-B5-Pad17)") (class "Default")
      (node (ref "LS3") (pin "17") (pinfunction "B5_17") (pintype "bidirectional"))
    )
    (net (code "155") (name "unconnected-(LS3-B6-Pad16)") (class "Default")
      (node (ref "LS3") (pin "16") (pinfunction "B6_16") (pintype "bidirectional"))
    )
    (net (code "156") (name "unconnected-(LS3-B7-Pad15)") (class "Default")
      (node (ref "LS3") (pin "15") (pinfunction "B7_15") (pintype "bidirectional"))
    )
    (net (code "157") (name "unconnected-(LS3-B8-Pad14)") (class "Default")
      (node (ref "LS3") (pin "14") (pinfunction "B8_14") (pintype "bidirectional"))
    )
    (net (code "158") (name "unconnected-(LS4-B2-Pad20)") (class "Default")
      (node (ref "LS4") (pin "20") (pinfunction "B2_20") (pintype "bidirectional"))
    )
    (net (code "159") (name "unconnected-(LS4-B3-Pad19)") (class "Default")
      (node (ref "LS4") (pin "19") (pinfunction "B3_19") (pintype "bidirectional"))
    )
    (net (code "160") (name "unconnected-(LS4-B4-Pad18)") (class "Default")
      (node (ref "LS4") (pin "18") (pinfunction "B4_18") (pintype "bidirectional"))
    )
    (net (code "161") (name "unconnected-(LS4-B5-Pad17)") (class "Default")
      (node (ref "LS4") (pin "17") (pinfunction "B5_17") (pintype "bidirectional"))
    )
    (net (code "162") (name "unconnected-(LS4-B6-Pad16)") (class "Default")
      (node (ref "LS4") (pin "16") (pinfunction "B6_16") (pintype "bidirectional"))
    )
    (net (code "163") (name "unconnected-(LS4-B7-Pad15)") (class "Default")
      (node (ref "LS4") (pin "15") (pinfunction "B7_15") (pintype "bidirectional"))
    )
    (net (code "164") (name "unconnected-(LS4-B8-Pad14)") (class "Default")
      (node (ref "LS4") (pin "14") (pinfunction "B8_14") (pintype "bidirectional"))
    )
    (net (code "165") (name "unconnected-(U3-PWRG-Pad5)") (class "Default")
      (node (ref "U3") (pin "5") (pinfunction "PWRG_5") (pintype "bidirectional"))
    )
    (net (code "166") (name "unconnected-(U4-PWRG-Pad5)") (class "Default")
      (node (ref "U4") (pin "5") (pinfunction "PWRG_5") (pintype "bidirectional"))
    )
  )
)
